# FY_-_OPTO_BOARD_3_GEN.net
KiCad netlist of a schematic drawn in EAGLE
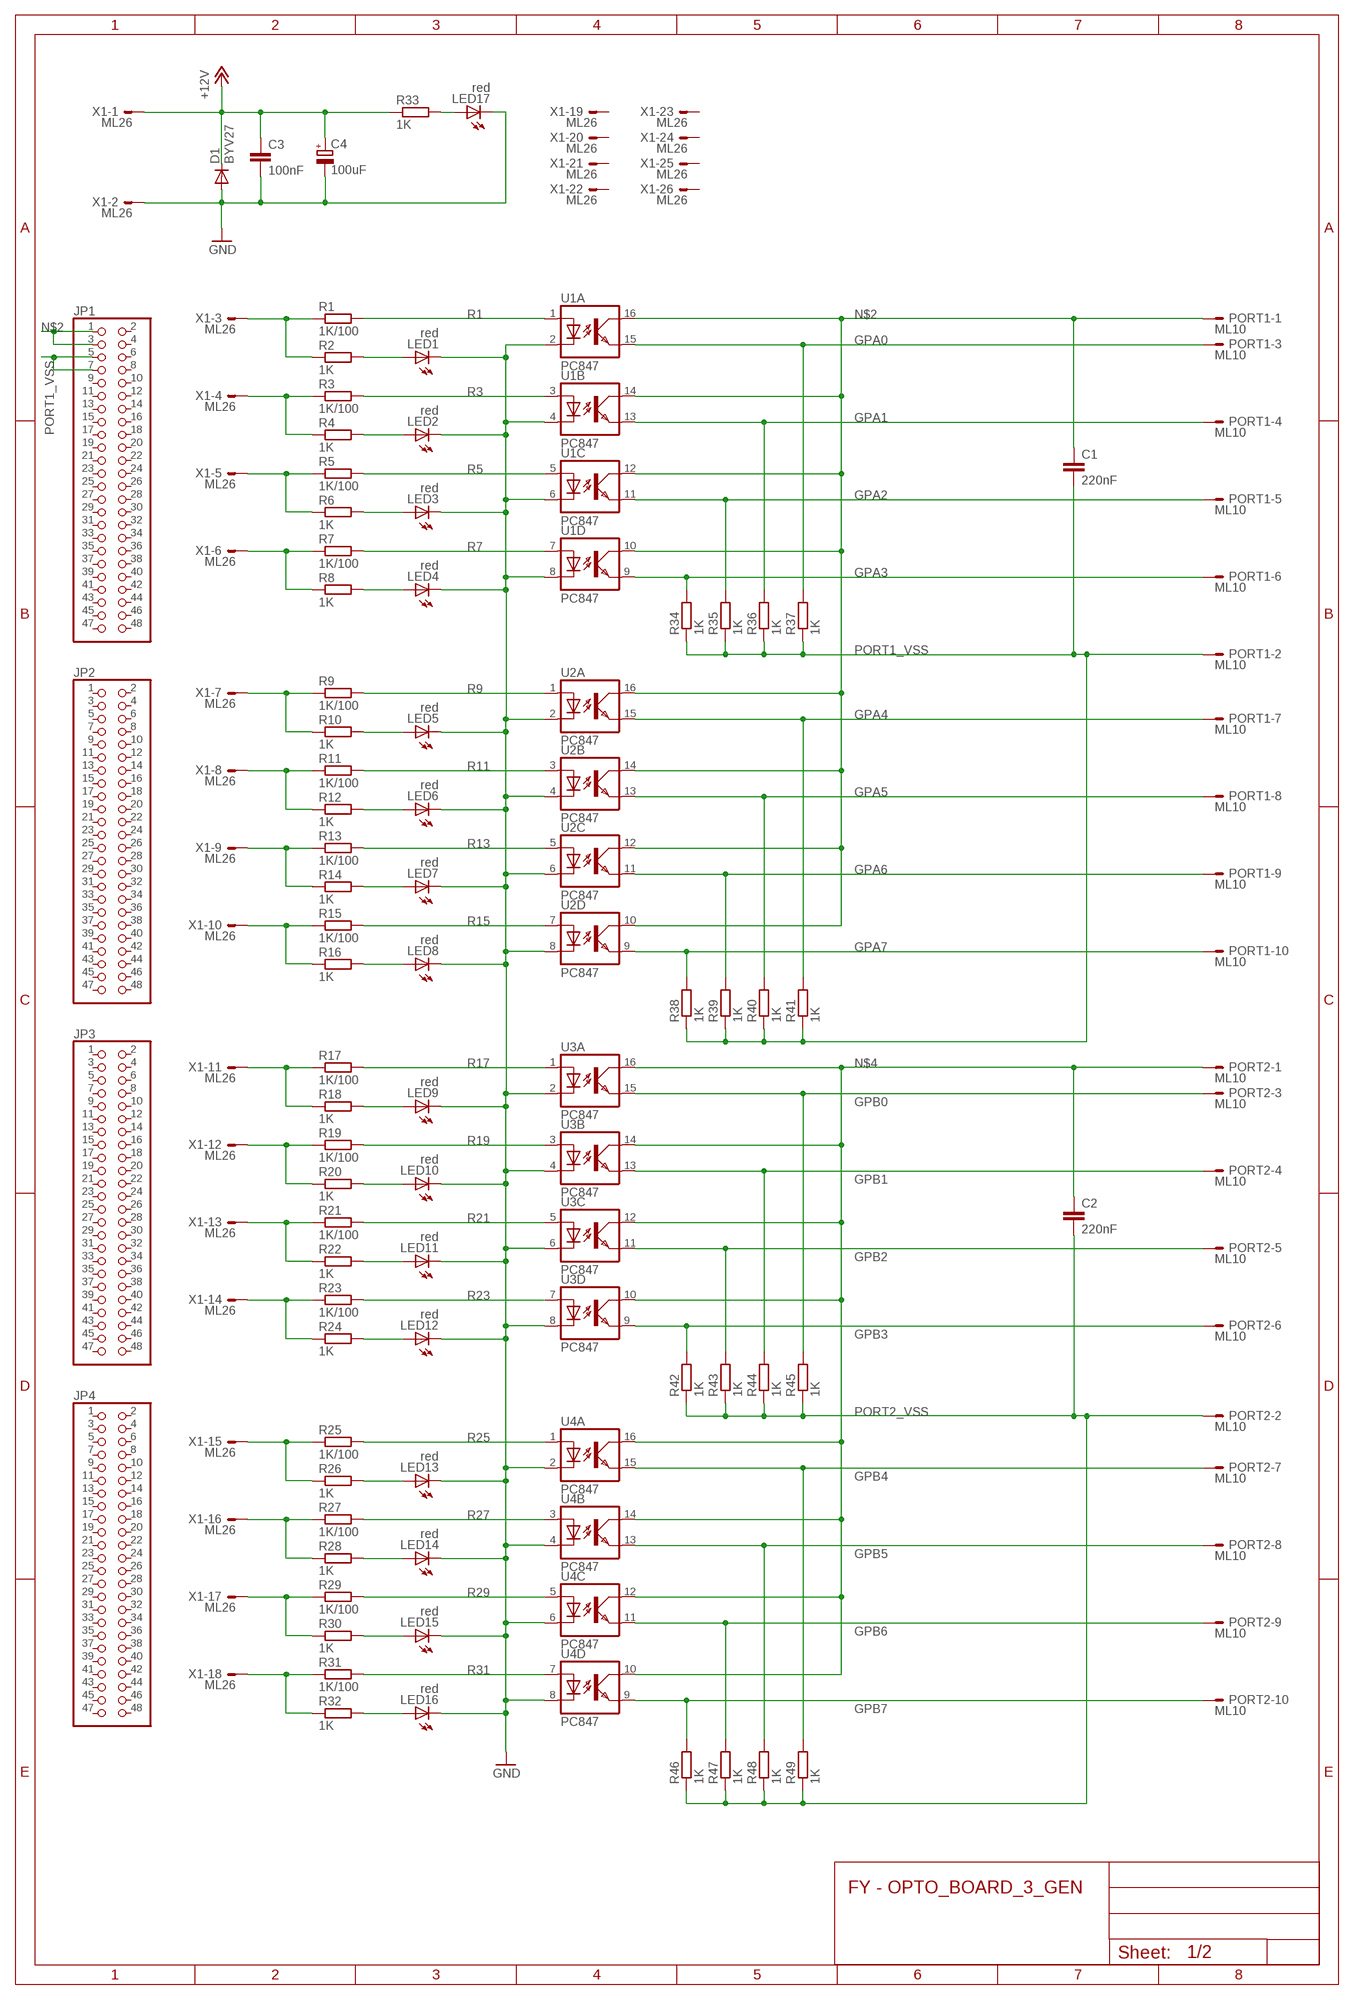
[diagram p0: schematic, sheet 1]
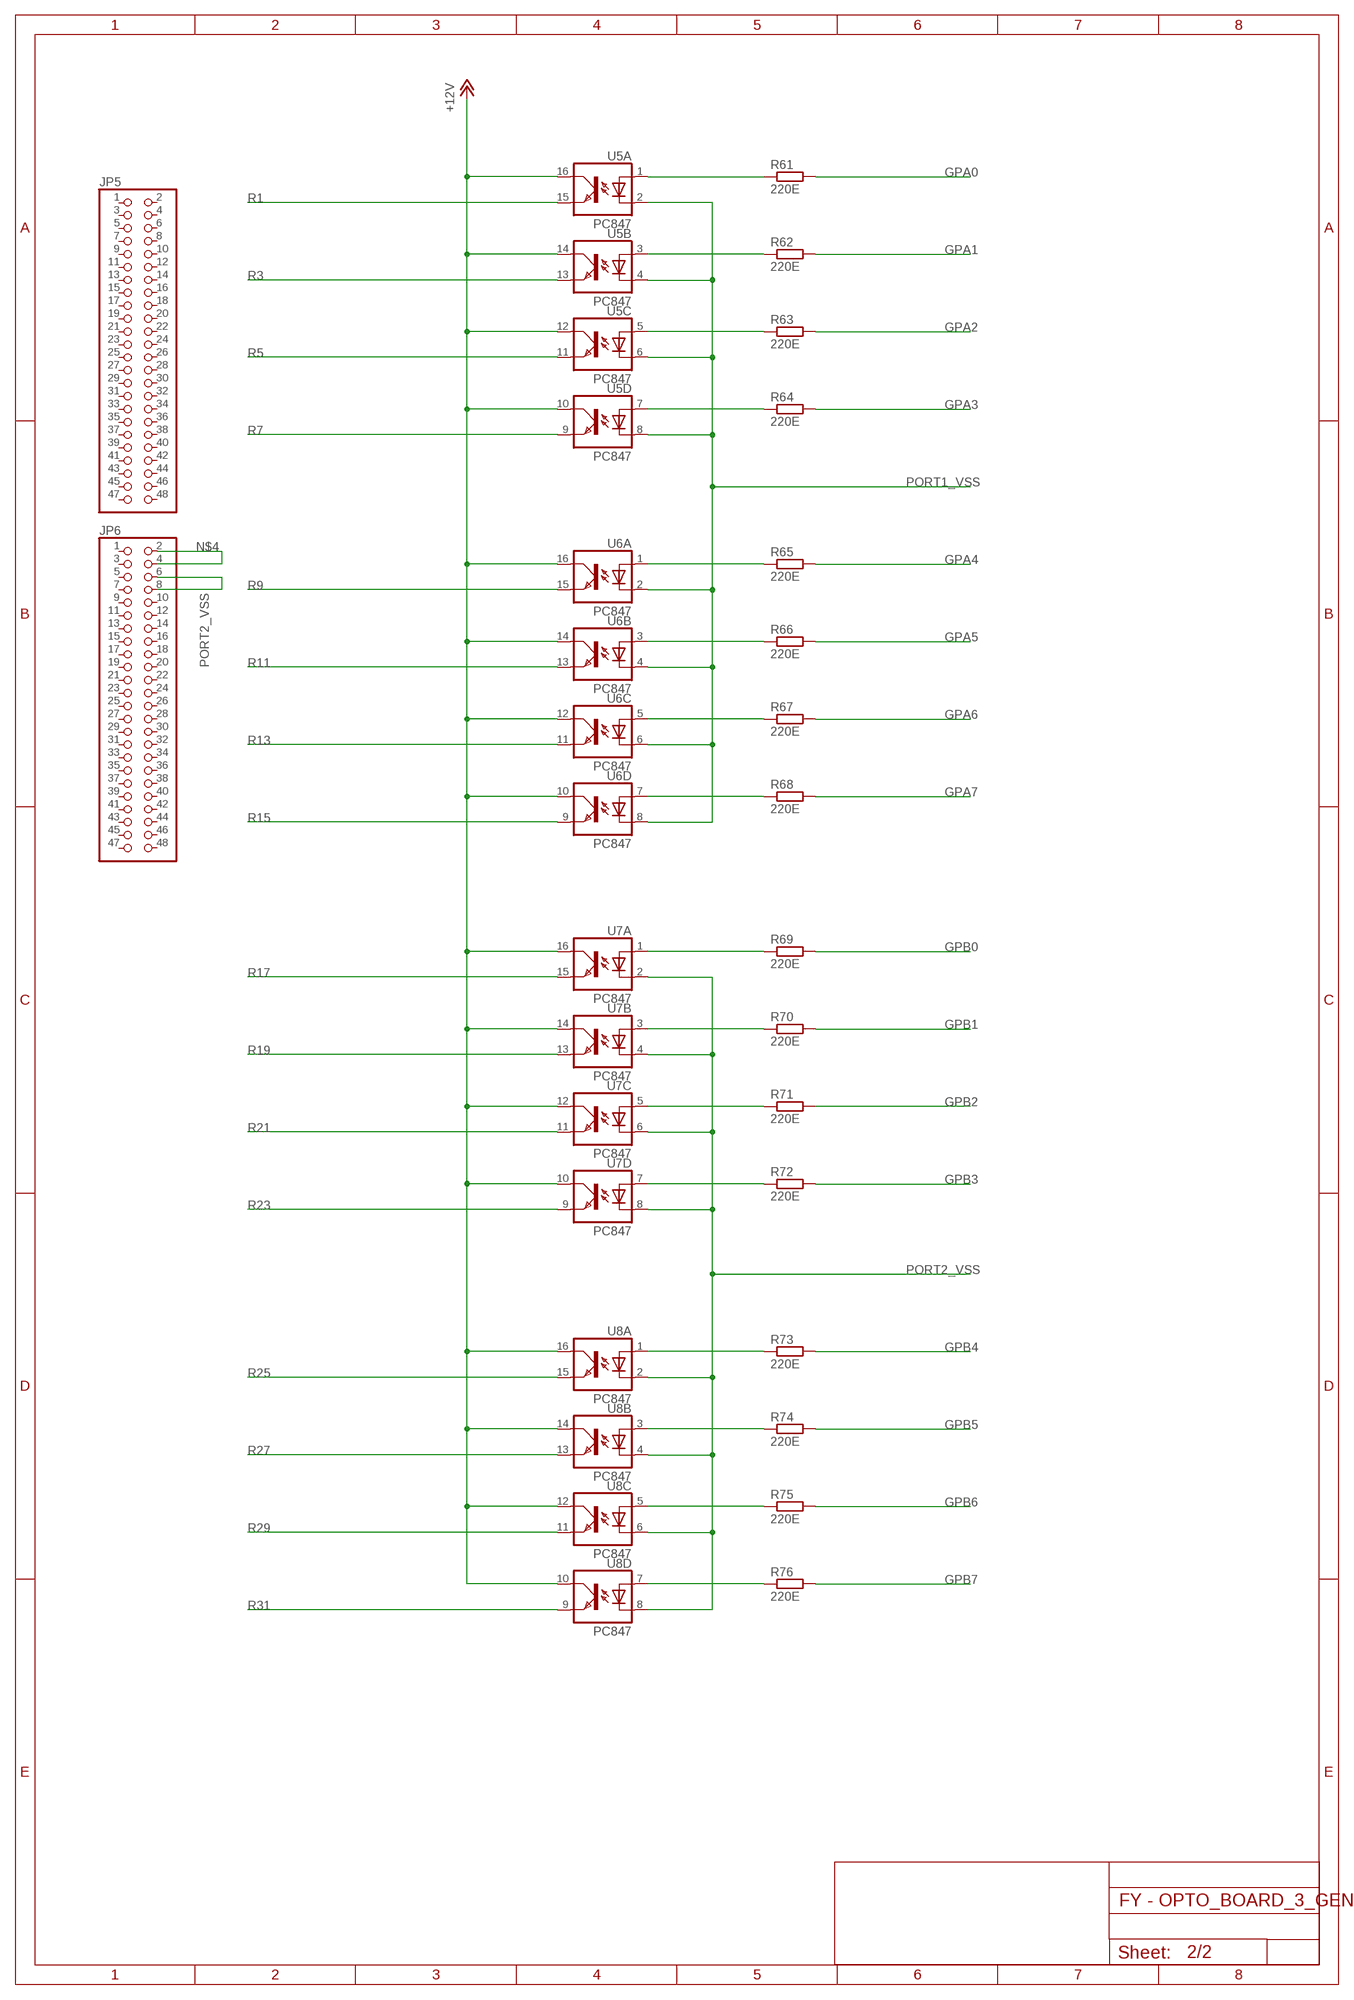
[diagram p1: schematic, sheet 2]

(export (version "E")
  (design (tool "Eeschema 10.0.6"))
  (components
    (comp (ref "JP5")
      (value "PINHD-2X24")
      (footprint "eagle-import:2X24")
      (libsource (lib "eagle-import") (part "PINHD-2X24"))
    )
    (comp (ref "JP6")
      (value "PINHD-2X24")
      (footprint "eagle-import:2X24")
      (libsource (lib "eagle-import") (part "PINHD-2X24"))
    )
    (comp (ref "R61")
      (value "220E")
      (footprint "eagle-import:0207_10")
      (libsource (lib "eagle-import") (part "R-EU_0207/10"))
    )
    (comp (ref "R62")
      (value "220E")
      (footprint "eagle-import:0207_10")
      (libsource (lib "eagle-import") (part "R-EU_0207/10"))
    )
    (comp (ref "R63")
      (value "220E")
      (footprint "eagle-import:0207_10")
      (libsource (lib "eagle-import") (part "R-EU_0207/10"))
    )
    (comp (ref "R64")
      (value "220E")
      (footprint "eagle-import:0207_10")
      (libsource (lib "eagle-import") (part "R-EU_0207/10"))
    )
    (comp (ref "R65")
      (value "220E")
      (footprint "eagle-import:0207_10")
      (libsource (lib "eagle-import") (part "R-EU_0207/10"))
    )
    (comp (ref "R66")
      (value "220E")
      (footprint "eagle-import:0207_10")
      (libsource (lib "eagle-import") (part "R-EU_0207/10"))
    )
    (comp (ref "R67")
      (value "220E")
      (footprint "eagle-import:0207_10")
      (libsource (lib "eagle-import") (part "R-EU_0207/10"))
    )
    (comp (ref "R68")
      (value "220E")
      (footprint "eagle-import:0207_10")
      (libsource (lib "eagle-import") (part "R-EU_0207/10"))
    )
    (comp (ref "R69")
      (value "220E")
      (footprint "eagle-import:0207_10")
      (libsource (lib "eagle-import") (part "R-EU_0207/10"))
    )
    (comp (ref "R70")
      (value "220E")
      (footprint "eagle-import:0207_10")
      (libsource (lib "eagle-import") (part "R-EU_0207/10"))
    )
    (comp (ref "R71")
      (value "220E")
      (footprint "eagle-import:0207_10")
      (libsource (lib "eagle-import") (part "R-EU_0207/10"))
    )
    (comp (ref "R72")
      (value "220E")
      (footprint "eagle-import:0207_10")
      (libsource (lib "eagle-import") (part "R-EU_0207/10"))
    )
    (comp (ref "R73")
      (value "220E")
      (footprint "eagle-import:0207_10")
      (libsource (lib "eagle-import") (part "R-EU_0207/10"))
    )
    (comp (ref "R74")
      (value "220E")
      (footprint "eagle-import:0207_10")
      (libsource (lib "eagle-import") (part "R-EU_0207/10"))
    )
    (comp (ref "R75")
      (value "220E")
      (footprint "eagle-import:0207_10")
      (libsource (lib "eagle-import") (part "R-EU_0207/10"))
    )
    (comp (ref "R76")
      (value "220E")
      (footprint "eagle-import:0207_10")
      (libsource (lib "eagle-import") (part "R-EU_0207/10"))
    )
    (comp (ref "U5")
      (value "PC847")
      (footprint "eagle-import:DIL16")
      (libsource (lib "eagle-import") (part "PC847"))
    )
    (comp (ref "U6")
      (value "PC847")
      (footprint "eagle-import:DIL16")
      (libsource (lib "eagle-import") (part "PC847"))
    )
    (comp (ref "U7")
      (value "PC847")
      (footprint "eagle-import:DIL16")
      (libsource (lib "eagle-import") (part "PC847"))
    )
    (comp (ref "U8")
      (value "PC847")
      (footprint "eagle-import:DIL16")
      (libsource (lib "eagle-import") (part "PC847"))
    )
    (comp (ref "C1")
      (value "220nF")
      (footprint "eagle-import:C050-025X075")
      (libsource (lib "eagle-import") (part "C-EU050-025X075"))
    )
    (comp (ref "C2")
      (value "220nF")
      (footprint "eagle-import:C050-025X075")
      (libsource (lib "eagle-import") (part "C-EU050-025X075"))
    )
    (comp (ref "C3")
      (value "100nF")
      (footprint "eagle-import:C050-025X075")
      (libsource (lib "eagle-import") (part "C-EU050-025X075"))
    )
    (comp (ref "C4")
      (value "100uF")
      (footprint "eagle-import:E5-8,5")
      (libsource (lib "eagle-import") (part "CPOL-EUE5-8.5"))
    )
    (comp (ref "D1")
      (value "BYV27")
      (footprint "eagle-import:SOD57-10")
      (libsource (lib "eagle-import") (part "BYV27"))
    )
    (comp (ref "JP1")
      (value "PINHD-2X24")
      (footprint "eagle-import:2X24")
      (libsource (lib "eagle-import") (part "PINHD-2X24"))
    )
    (comp (ref "JP2")
      (value "PINHD-2X24")
      (footprint "eagle-import:2X24")
      (libsource (lib "eagle-import") (part "PINHD-2X24"))
    )
    (comp (ref "JP3")
      (value "PINHD-2X24")
      (footprint "eagle-import:2X24")
      (libsource (lib "eagle-import") (part "PINHD-2X24"))
    )
    (comp (ref "JP4")
      (value "PINHD-2X24")
      (footprint "eagle-import:2X24")
      (libsource (lib "eagle-import") (part "PINHD-2X24"))
    )
    (comp (ref "LED1")
      (value "red")
      (footprint "eagle-import:LED3MM")
      (libsource (lib "eagle-import") (part "LED3MM"))
    )
    (comp (ref "LED2")
      (value "red")
      (footprint "eagle-import:LED3MM")
      (libsource (lib "eagle-import") (part "LED3MM"))
    )
    (comp (ref "LED3")
      (value "red")
      (footprint "eagle-import:LED3MM")
      (libsource (lib "eagle-import") (part "LED3MM"))
    )
    (comp (ref "LED4")
      (value "red")
      (footprint "eagle-import:LED3MM")
      (libsource (lib "eagle-import") (part "LED3MM"))
    )
    (comp (ref "LED5")
      (value "red")
      (footprint "eagle-import:LED3MM")
      (libsource (lib "eagle-import") (part "LED3MM"))
    )
    (comp (ref "LED6")
      (value "red")
      (footprint "eagle-import:LED3MM")
      (libsource (lib "eagle-import") (part "LED3MM"))
    )
    (comp (ref "LED7")
      (value "red")
      (footprint "eagle-import:LED3MM")
      (libsource (lib "eagle-import") (part "LED3MM"))
    )
    (comp (ref "LED8")
      (value "red")
      (footprint "eagle-import:LED3MM")
      (libsource (lib "eagle-import") (part "LED3MM"))
    )
    (comp (ref "LED9")
      (value "red")
      (footprint "eagle-import:LED3MM")
      (libsource (lib "eagle-import") (part "LED3MM"))
    )
    (comp (ref "LED10")
      (value "red")
      (footprint "eagle-import:LED3MM")
      (libsource (lib "eagle-import") (part "LED3MM"))
    )
    (comp (ref "LED11")
      (value "red")
      (footprint "eagle-import:LED3MM")
      (libsource (lib "eagle-import") (part "LED3MM"))
    )
    (comp (ref "LED12")
      (value "red")
      (footprint "eagle-import:LED3MM")
      (libsource (lib "eagle-import") (part "LED3MM"))
    )
    (comp (ref "LED13")
      (value "red")
      (footprint "eagle-import:LED3MM")
      (libsource (lib "eagle-import") (part "LED3MM"))
    )
    (comp (ref "LED14")
      (value "red")
      (footprint "eagle-import:LED3MM")
      (libsource (lib "eagle-import") (part "LED3MM"))
    )
    (comp (ref "LED15")
      (value "red")
      (footprint "eagle-import:LED3MM")
      (libsource (lib "eagle-import") (part "LED3MM"))
    )
    (comp (ref "LED16")
      (value "red")
      (footprint "eagle-import:LED3MM")
      (libsource (lib "eagle-import") (part "LED3MM"))
    )
    (comp (ref "LED17")
      (value "red")
      (footprint "eagle-import:LED3MM")
      (libsource (lib "eagle-import") (part "LED3MM"))
    )
    (comp (ref "PORT1")
      (value "ML10")
      (footprint "eagle-import:ML10")
      (libsource (lib "eagle-import") (part "ML10?E"))
    )
    (comp (ref "PORT2")
      (value "ML10")
      (footprint "eagle-import:ML10")
      (libsource (lib "eagle-import") (part "ML10?E"))
    )
    (comp (ref "R1")
      (value "1K/100")
      (footprint "eagle-import:0207_10")
      (libsource (lib "eagle-import") (part "R-EU_0207/10"))
    )
    (comp (ref "R2")
      (value "1K")
      (footprint "eagle-import:0207_10")
      (libsource (lib "eagle-import") (part "R-EU_0207/10"))
    )
    (comp (ref "R3")
      (value "1K/100")
      (footprint "eagle-import:0207_10")
      (libsource (lib "eagle-import") (part "R-EU_0207/10"))
    )
    (comp (ref "R4")
      (value "1K")
      (footprint "eagle-import:0207_10")
      (libsource (lib "eagle-import") (part "R-EU_0207/10"))
    )
    (comp (ref "R5")
      (value "1K/100")
      (footprint "eagle-import:0207_10")
      (libsource (lib "eagle-import") (part "R-EU_0207/10"))
    )
    (comp (ref "R6")
      (value "1K")
      (footprint "eagle-import:0207_10")
      (libsource (lib "eagle-import") (part "R-EU_0207/10"))
    )
    (comp (ref "R7")
      (value "1K/100")
      (footprint "eagle-import:0207_10")
      (libsource (lib "eagle-import") (part "R-EU_0207/10"))
    )
    (comp (ref "R8")
      (value "1K")
      (footprint "eagle-import:0207_10")
      (libsource (lib "eagle-import") (part "R-EU_0207/10"))
    )
    (comp (ref "R9")
      (value "1K/100")
      (footprint "eagle-import:0207_10")
      (libsource (lib "eagle-import") (part "R-EU_0207/10"))
    )
    (comp (ref "R10")
      (value "1K")
      (footprint "eagle-import:0207_10")
      (libsource (lib "eagle-import") (part "R-EU_0207/10"))
    )
    (comp (ref "R11")
      (value "1K/100")
      (footprint "eagle-import:0207_10")
      (libsource (lib "eagle-import") (part "R-EU_0207/10"))
    )
    (comp (ref "R12")
      (value "1K")
      (footprint "eagle-import:0207_10")
      (libsource (lib "eagle-import") (part "R-EU_0207/10"))
    )
    (comp (ref "R13")
      (value "1K/100")
      (footprint "eagle-import:0207_10")
      (libsource (lib "eagle-import") (part "R-EU_0207/10"))
    )
    (comp (ref "R14")
      (value "1K")
      (footprint "eagle-import:0207_10")
      (libsource (lib "eagle-import") (part "R-EU_0207/10"))
    )
    (comp (ref "R15")
      (value "1K/100")
      (footprint "eagle-import:0207_10")
      (libsource (lib "eagle-import") (part "R-EU_0207/10"))
    )
    (comp (ref "R16")
      (value "1K")
      (footprint "eagle-import:0207_10")
      (libsource (lib "eagle-import") (part "R-EU_0207/10"))
    )
    (comp (ref "R17")
      (value "1K/100")
      (footprint "eagle-import:0207_10")
      (libsource (lib "eagle-import") (part "R-EU_0207/10"))
    )
    (comp (ref "R18")
      (value "1K")
      (footprint "eagle-import:0207_10")
      (libsource (lib "eagle-import") (part "R-EU_0207/10"))
    )
    (comp (ref "R19")
      (value "1K/100")
      (footprint "eagle-import:0207_10")
      (libsource (lib "eagle-import") (part "R-EU_0207/10"))
    )
    (comp (ref "R20")
      (value "1K")
      (footprint "eagle-import:0207_10")
      (libsource (lib "eagle-import") (part "R-EU_0207/10"))
    )
    (comp (ref "R21")
      (value "1K/100")
      (footprint "eagle-import:0207_10")
      (libsource (lib "eagle-import") (part "R-EU_0207/10"))
    )
    (comp (ref "R22")
      (value "1K")
      (footprint "eagle-import:0207_10")
      (libsource (lib "eagle-import") (part "R-EU_0207/10"))
    )
    (comp (ref "R23")
      (value "1K/100")
      (footprint "eagle-import:0207_10")
      (libsource (lib "eagle-import") (part "R-EU_0207/10"))
    )
    (comp (ref "R24")
      (value "1K")
      (footprint "eagle-import:0207_10")
      (libsource (lib "eagle-import") (part "R-EU_0207/10"))
    )
    (comp (ref "R25")
      (value "1K/100")
      (footprint "eagle-import:0207_10")
      (libsource (lib "eagle-import") (part "R-EU_0207/10"))
    )
    (comp (ref "R26")
      (value "1K")
      (footprint "eagle-import:0207_10")
      (libsource (lib "eagle-import") (part "R-EU_0207/10"))
    )
    (comp (ref "R27")
      (value "1K/100")
      (footprint "eagle-import:0207_10")
      (libsource (lib "eagle-import") (part "R-EU_0207/10"))
    )
    (comp (ref "R28")
      (value "1K")
      (footprint "eagle-import:0207_10")
      (libsource (lib "eagle-import") (part "R-EU_0207/10"))
    )
    (comp (ref "R29")
      (value "1K/100")
      (footprint "eagle-import:0207_10")
      (libsource (lib "eagle-import") (part "R-EU_0207/10"))
    )
    (comp (ref "R30")
      (value "1K")
      (footprint "eagle-import:0207_10")
      (libsource (lib "eagle-import") (part "R-EU_0207/10"))
    )
    (comp (ref "R31")
      (value "1K/100")
      (footprint "eagle-import:0207_10")
      (libsource (lib "eagle-import") (part "R-EU_0207/10"))
    )
    (comp (ref "R32")
      (value "1K")
      (footprint "eagle-import:0207_10")
      (libsource (lib "eagle-import") (part "R-EU_0207/10"))
    )
    (comp (ref "R33")
      (value "1K")
      (footprint "eagle-import:0207_10")
      (libsource (lib "eagle-import") (part "R-EU_0207/10"))
    )
    (comp (ref "R34")
      (value "1K")
      (footprint "eagle-import:0207_10")
      (libsource (lib "eagle-import") (part "R-EU_0207/10"))
    )
    (comp (ref "R35")
      (value "1K")
      (footprint "eagle-import:0207_10")
      (libsource (lib "eagle-import") (part "R-EU_0207/10"))
    )
    (comp (ref "R36")
      (value "1K")
      (footprint "eagle-import:0207_10")
      (libsource (lib "eagle-import") (part "R-EU_0207/10"))
    )
    (comp (ref "R37")
      (value "1K")
      (footprint "eagle-import:0207_10")
      (libsource (lib "eagle-import") (part "R-EU_0207/10"))
    )
    (comp (ref "R38")
      (value "1K")
      (footprint "eagle-import:0207_10")
      (libsource (lib "eagle-import") (part "R-EU_0207/10"))
    )
    (comp (ref "R39")
      (value "1K")
      (footprint "eagle-import:0207_10")
      (libsource (lib "eagle-import") (part "R-EU_0207/10"))
    )
    (comp (ref "R40")
      (value "1K")
      (footprint "eagle-import:0207_10")
      (libsource (lib "eagle-import") (part "R-EU_0207/10"))
    )
    (comp (ref "R41")
      (value "1K")
      (footprint "eagle-import:0207_10")
      (libsource (lib "eagle-import") (part "R-EU_0207/10"))
    )
    (comp (ref "R42")
      (value "1K")
      (footprint "eagle-import:0207_10")
      (libsource (lib "eagle-import") (part "R-EU_0207/10"))
    )
    (comp (ref "R43")
      (value "1K")
      (footprint "eagle-import:0207_10")
      (libsource (lib "eagle-import") (part "R-EU_0207/10"))
    )
    (comp (ref "R44")
      (value "1K")
      (footprint "eagle-import:0207_10")
      (libsource (lib "eagle-import") (part "R-EU_0207/10"))
    )
    (comp (ref "R45")
      (value "1K")
      (footprint "eagle-import:0207_10")
      (libsource (lib "eagle-import") (part "R-EU_0207/10"))
    )
    (comp (ref "R46")
      (value "1K")
      (footprint "eagle-import:0207_10")
      (libsource (lib "eagle-import") (part "R-EU_0207/10"))
    )
    (comp (ref "R47")
      (value "1K")
      (footprint "eagle-import:0207_10")
      (libsource (lib "eagle-import") (part "R-EU_0207/10"))
    )
    (comp (ref "R48")
      (value "1K")
      (footprint "eagle-import:0207_10")
      (libsource (lib "eagle-import") (part "R-EU_0207/10"))
    )
    (comp (ref "R49")
      (value "1K")
      (footprint "eagle-import:0207_10")
      (libsource (lib "eagle-import") (part "R-EU_0207/10"))
    )
    (comp (ref "U1")
      (value "PC847")
      (footprint "eagle-import:DIL16")
      (libsource (lib "eagle-import") (part "PC847"))
    )
    (comp (ref "U2")
      (value "PC847")
      (footprint "eagle-import:DIL16")
      (libsource (lib "eagle-import") (part "PC847"))
    )
    (comp (ref "U3")
      (value "PC847")
      (footprint "eagle-import:DIL16")
      (libsource (lib "eagle-import") (part "PC847"))
    )
    (comp (ref "U4")
      (value "PC847")
      (footprint "eagle-import:DIL16")
      (libsource (lib "eagle-import") (part "PC847"))
    )
    (comp (ref "X1")
      (value "ML26")
      (footprint "eagle-import:ML26")
      (libsource (lib "eagle-import") (part "ML26?E"))
    )
  )
  (nets
    (net (code "1") (name "+12V") (class "Default")
      (node (ref "C3") (pin "1") (pinfunction "1_1") (pintype "passive"))
      (node (ref "C4") (pin "+") (pinfunction "+_+") (pintype "passive"))
      (node (ref "D1") (pin "C") (pinfunction "C_C") (pintype "passive"))
      (node (ref "R33") (pin "1") (pinfunction "1_1") (pintype "passive"))
      (node (ref "U5") (pin "10") (pinfunction "COL_10") (pintype "passive"))
      (node (ref "U5") (pin "12") (pinfunction "COL_12") (pintype "passive"))
      (node (ref "U5") (pin "14") (pinfunction "COL_14") (pintype "passive"))
      (node (ref "U5") (pin "16") (pinfunction "COL_16") (pintype "passive"))
      (node (ref "U6") (pin "10") (pinfunction "COL_10") (pintype "passive"))
      (node (ref "U6") (pin "12") (pinfunction "COL_12") (pintype "passive"))
      (node (ref "U6") (pin "14") (pinfunction "COL_14") (pintype "passive"))
      (node (ref "U6") (pin "16") (pinfunction "COL_16") (pintype "passive"))
      (node (ref "U7") (pin "10") (pinfunction "COL_10") (pintype "passive"))
      (node (ref "U7") (pin "12") (pinfunction "COL_12") (pintype "passive"))
      (node (ref "U7") (pin "14") (pinfunction "COL_14") (pintype "passive"))
      (node (ref "U7") (pin "16") (pinfunction "COL_16") (pintype "passive"))
      (node (ref "U8") (pin "10") (pinfunction "COL_10") (pintype "passive"))
      (node (ref "U8") (pin "12") (pinfunction "COL_12") (pintype "passive"))
      (node (ref "U8") (pin "14") (pinfunction "COL_14") (pintype "passive"))
      (node (ref "U8") (pin "16") (pinfunction "COL_16") (pintype "passive"))
      (node (ref "X1") (pin "1") (pinfunction "S_1") (pintype "passive"))
    )
    (net (code "2") (name "GND") (class "Default")
      (node (ref "C3") (pin "2") (pinfunction "2_2") (pintype "passive"))
      (node (ref "C4") (pin "-") (pinfunction "-_-") (pintype "passive"))
      (node (ref "D1") (pin "A") (pinfunction "A_A") (pintype "passive"))
      (node (ref "LED1") (pin "K") (pinfunction "C_K") (pintype "passive"))
      (node (ref "LED10") (pin "K") (pinfunction "C_K") (pintype "passive"))
      (node (ref "LED11") (pin "K") (pinfunction "C_K") (pintype "passive"))
      (node (ref "LED12") (pin "K") (pinfunction "C_K") (pintype "passive"))
      (node (ref "LED13") (pin "K") (pinfunction "C_K") (pintype "passive"))
      (node (ref "LED14") (pin "K") (pinfunction "C_K") (pintype "passive"))
      (node (ref "LED15") (pin "K") (pinfunction "C_K") (pintype "passive"))
      (node (ref "LED16") (pin "K") (pinfunction "C_K") (pintype "passive"))
      (node (ref "LED17") (pin "K") (pinfunction "C_K") (pintype "passive"))
      (node (ref "LED2") (pin "K") (pinfunction "C_K") (pintype "passive"))
      (node (ref "LED3") (pin "K") (pinfunction "C_K") (pintype "passive"))
      (node (ref "LED4") (pin "K") (pinfunction "C_K") (pintype "passive"))
      (node (ref "LED5") (pin "K") (pinfunction "C_K") (pintype "passive"))
      (node (ref "LED6") (pin "K") (pinfunction "C_K") (pintype "passive"))
      (node (ref "LED7") (pin "K") (pinfunction "C_K") (pintype "passive"))
      (node (ref "LED8") (pin "K") (pinfunction "C_K") (pintype "passive"))
      (node (ref "LED9") (pin "K") (pinfunction "C_K") (pintype "passive"))
      (node (ref "U1") (pin "2") (pinfunction "C_2") (pintype "passive"))
      (node (ref "U1") (pin "4") (pinfunction "C_4") (pintype "passive"))
      (node (ref "U1") (pin "6") (pinfunction "C_6") (pintype "passive"))
      (node (ref "U1") (pin "8") (pinfunction "C_8") (pintype "passive"))
      (node (ref "U2") (pin "2") (pinfunction "C_2") (pintype "passive"))
      (node (ref "U2") (pin "4") (pinfunction "C_4") (pintype "passive"))
      (node (ref "U2") (pin "6") (pinfunction "C_6") (pintype "passive"))
      (node (ref "U2") (pin "8") (pinfunction "C_8") (pintype "passive"))
      (node (ref "U3") (pin "2") (pinfunction "C_2") (pintype "passive"))
      (node (ref "U3") (pin "4") (pinfunction "C_4") (pintype "passive"))
      (node (ref "U3") (pin "6") (pinfunction "C_6") (pintype "passive"))
      (node (ref "U3") (pin "8") (pinfunction "C_8") (pintype "passive"))
      (node (ref "U4") (pin "2") (pinfunction "C_2") (pintype "passive"))
      (node (ref "U4") (pin "4") (pinfunction "C_4") (pintype "passive"))
      (node (ref "U4") (pin "6") (pinfunction "C_6") (pintype "passive"))
      (node (ref "U4") (pin "8") (pinfunction "C_8") (pintype "passive"))
      (node (ref "X1") (pin "2") (pinfunction "S_2") (pintype "passive"))
    )
    (net (code "3") (name "GPA0") (class "Default")
      (node (ref "PORT1") (pin "3") (pinfunction "S_3") (pintype "passive"))
      (node (ref "R37") (pin "2") (pinfunction "2_2") (pintype "passive"))
      (node (ref "R61") (pin "2") (pinfunction "2_2") (pintype "passive"))
      (node (ref "U1") (pin "15") (pinfunction "EMIT_15") (pintype "passive"))
    )
    (net (code "4") (name "GPA1") (class "Default")
      (node (ref "PORT1") (pin "4") (pinfunction "S_4") (pintype "passive"))
      (node (ref "R36") (pin "2") (pinfunction "2_2") (pintype "passive"))
      (node (ref "R62") (pin "2") (pinfunction "2_2") (pintype "passive"))
      (node (ref "U1") (pin "13") (pinfunction "EMIT_13") (pintype "passive"))
    )
    (net (code "5") (name "GPA2") (class "Default")
      (node (ref "PORT1") (pin "5") (pinfunction "S_5") (pintype "passive"))
      (node (ref "R35") (pin "2") (pinfunction "2_2") (pintype "passive"))
      (node (ref "R63") (pin "2") (pinfunction "2_2") (pintype "passive"))
      (node (ref "U1") (pin "11") (pinfunction "EMIT_11") (pintype "passive"))
    )
    (net (code "6") (name "GPA3") (class "Default")
      (node (ref "PORT1") (pin "6") (pinfunction "S_6") (pintype "passive"))
      (node (ref "R34") (pin "2") (pinfunction "2_2") (pintype "passive"))
      (node (ref "R64") (pin "2") (pinfunction "2_2") (pintype "passive"))
      (node (ref "U1") (pin "9") (pinfunction "EMIT_9") (pintype "passive"))
    )
    (net (code "7") (name "GPA4") (class "Default")
      (node (ref "PORT1") (pin "7") (pinfunction "S_7") (pintype "passive"))
      (node (ref "R41") (pin "2") (pinfunction "2_2") (pintype "passive"))
      (node (ref "R65") (pin "2") (pinfunction "2_2") (pintype "passive"))
      (node (ref "U2") (pin "15") (pinfunction "EMIT_15") (pintype "passive"))
    )
    (net (code "8") (name "GPA5") (class "Default")
      (node (ref "PORT1") (pin "8") (pinfunction "S_8") (pintype "passive"))
      (node (ref "R40") (pin "2") (pinfunction "2_2") (pintype "passive"))
      (node (ref "R66") (pin "2") (pinfunction "2_2") (pintype "passive"))
      (node (ref "U2") (pin "13") (pinfunction "EMIT_13") (pintype "passive"))
    )
    (net (code "9") (name "GPA6") (class "Default")
      (node (ref "PORT1") (pin "9") (pinfunction "S_9") (pintype "passive"))
      (node (ref "R39") (pin "2") (pinfunction "2_2") (pintype "passive"))
      (node (ref "R67") (pin "2") (pinfunction "2_2") (pintype "passive"))
      (node (ref "U2") (pin "11") (pinfunction "EMIT_11") (pintype "passive"))
    )
    (net (code "10") (name "GPA7") (class "Default")
      (node (ref "PORT1") (pin "10") (pinfunction "S_10") (pintype "passive"))
      (node (ref "R38") (pin "2") (pinfunction "2_2") (pintype "passive"))
      (node (ref "R68") (pin "2") (pinfunction "2_2") (pintype "passive"))
      (node (ref "U2") (pin "9") (pinfunction "EMIT_9") (pintype "passive"))
    )
    (net (code "11") (name "GPB0") (class "Default")
      (node (ref "PORT2") (pin "3") (pinfunction "S_3") (pintype "passive"))
      (node (ref "R45") (pin "2") (pinfunction "2_2") (pintype "passive"))
      (node (ref "R69") (pin "2") (pinfunction "2_2") (pintype "passive"))
      (node (ref "U3") (pin "15") (pinfunction "EMIT_15") (pintype "passive"))
    )
    (net (code "12") (name "GPB1") (class "Default")
      (node (ref "PORT2") (pin "4") (pinfunction "S_4") (pintype "passive"))
      (node (ref "R44") (pin "2") (pinfunction "2_2") (pintype "passive"))
      (node (ref "R70") (pin "2") (pinfunction "2_2") (pintype "passive"))
      (node (ref "U3") (pin "13") (pinfunction "EMIT_13") (pintype "passive"))
    )
    (net (code "13") (name "GPB2") (class "Default")
      (node (ref "PORT2") (pin "5") (pinfunction "S_5") (pintype "passive"))
      (node (ref "R43") (pin "2") (pinfunction "2_2") (pintype "passive"))
      (node (ref "R71") (pin "2") (pinfunction "2_2") (pintype "passive"))
      (node (ref "U3") (pin "11") (pinfunction "EMIT_11") (pintype "passive"))
    )
    (net (code "14") (name "GPB3") (class "Default")
      (node (ref "PORT2") (pin "6") (pinfunction "S_6") (pintype "passive"))
      (node (ref "R42") (pin "2") (pinfunction "2_2") (pintype "passive"))
      (node (ref "R72") (pin "2") (pinfunction "2_2") (pintype "passive"))
      (node (ref "U3") (pin "9") (pinfunction "EMIT_9") (pintype "passive"))
    )
    (net (code "15") (name "GPB4") (class "Default")
      (node (ref "PORT2") (pin "7") (pinfunction "S_7") (pintype "passive"))
      (node (ref "R49") (pin "2") (pinfunction "2_2") (pintype "passive"))
      (node (ref "R73") (pin "2") (pinfunction "2_2") (pintype "passive"))
      (node (ref "U4") (pin "15") (pinfunction "EMIT_15") (pintype "passive"))
    )
    (net (code "16") (name "GPB5") (class "Default")
      (node (ref "PORT2") (pin "8") (pinfunction "S_8") (pintype "passive"))
      (node (ref "R48") (pin "2") (pinfunction "2_2") (pintype "passive"))
      (node (ref "R74") (pin "2") (pinfunction "2_2") (pintype "passive"))
      (node (ref "U4") (pin "13") (pinfunction "EMIT_13") (pintype "passive"))
    )
    (net (code "17") (name "GPB6") (class "Default")
      (node (ref "PORT2") (pin "9") (pinfunction "S_9") (pintype "passive"))
      (node (ref "R47") (pin "2") (pinfunction "2_2") (pintype "passive"))
      (node (ref "R75") (pin "2") (pinfunction "2_2") (pintype "passive"))
      (node (ref "U4") (pin "11") (pinfunction "EMIT_11") (pintype "passive"))
    )
    (net (code "18") (name "GPB7") (class "Default")
      (node (ref "PORT2") (pin "10") (pinfunction "S_10") (pintype "passive"))
      (node (ref "R46") (pin "2") (pinfunction "2_2") (pintype "passive"))
      (node (ref "R76") (pin "2") (pinfunction "2_2") (pintype "passive"))
      (node (ref "U4") (pin "9") (pinfunction "EMIT_9") (pintype "passive"))
    )
    (net (code "19") (name "N$2") (class "Default")
      (node (ref "C1") (pin "1") (pinfunction "1_1") (pintype "passive"))
      (node (ref "JP1") (pin "1") (pinfunction "1_1") (pintype "passive"))
      (node (ref "JP1") (pin "3") (pinfunction "3_3") (pintype "passive"))
      (node (ref "PORT1") (pin "1") (pinfunction "S_1") (pintype "passive"))
      (node (ref "U1") (pin "10") (pinfunction "COL_10") (pintype "passive"))
      (node (ref "U1") (pin "12") (pinfunction "COL_12") (pintype "passive"))
      (node (ref "U1") (pin "14") (pinfunction "COL_14") (pintype "passive"))
      (node (ref "U1") (pin "16") (pinfunction "COL_16") (pintype "passive"))
      (node (ref "U2") (pin "10") (pinfunction "COL_10") (pintype "passive"))
      (node (ref "U2") (pin "12") (pinfunction "COL_12") (pintype "passive"))
      (node (ref "U2") (pin "14") (pinfunction "COL_14") (pintype "passive"))
      (node (ref "U2") (pin "16") (pinfunction "COL_16") (pintype "passive"))
    )
    (net (code "20") (name "N$4") (class "Default")
      (node (ref "C2") (pin "1") (pinfunction "1_1") (pintype "passive"))
      (node (ref "JP6") (pin "2") (pinfunction "2_2") (pintype "passive"))
      (node (ref "JP6") (pin "4") (pinfunction "4_4") (pintype "passive"))
      (node (ref "PORT2") (pin "1") (pinfunction "S_1") (pintype "passive"))
      (node (ref "U3") (pin "10") (pinfunction "COL_10") (pintype "passive"))
      (node (ref "U3") (pin "12") (pinfunction "COL_12") (pintype "passive"))
      (node (ref "U3") (pin "14") (pinfunction "COL_14") (pintype "passive"))
      (node (ref "U3") (pin "16") (pinfunction "COL_16") (pintype "passive"))
      (node (ref "U4") (pin "10") (pinfunction "COL_10") (pintype "passive"))
      (node (ref "U4") (pin "12") (pinfunction "COL_12") (pintype "passive"))
      (node (ref "U4") (pin "14") (pinfunction "COL_14") (pintype "passive"))
      (node (ref "U4") (pin "16") (pinfunction "COL_16") (pintype "passive"))
    )
    (net (code "21") (name "Net-(LED1-PadA)") (class "Default")
      (node (ref "LED1") (pin "A") (pinfunction "A_A") (pintype "passive"))
      (node (ref "R2") (pin "2") (pinfunction "2_2") (pintype "passive"))
    )
    (net (code "22") (name "Net-(LED2-PadA)") (class "Default")
      (node (ref "LED2") (pin "A") (pinfunction "A_A") (pintype "passive"))
      (node (ref "R4") (pin "2") (pinfunction "2_2") (pintype "passive"))
    )
    (net (code "23") (name "Net-(LED3-PadA)") (class "Default")
      (node (ref "LED3") (pin "A") (pinfunction "A_A") (pintype "passive"))
      (node (ref "R6") (pin "2") (pinfunction "2_2") (pintype "passive"))
    )
    (net (code "24") (name "Net-(LED4-PadA)") (class "Default")
      (node (ref "LED4") (pin "A") (pinfunction "A_A") (pintype "passive"))
      (node (ref "R8") (pin "2") (pinfunction "2_2") (pintype "passive"))
    )
    (net (code "25") (name "Net-(LED5-PadA)") (class "Default")
      (node (ref "LED5") (pin "A") (pinfunction "A_A") (pintype "passive"))
      (node (ref "R10") (pin "2") (pinfunction "2_2") (pintype "passive"))
    )
    (net (code "26") (name "Net-(LED6-PadA)") (class "Default")
      (node (ref "LED6") (pin "A") (pinfunction "A_A") (pintype "passive"))
      (node (ref "R12") (pin "2") (pinfunction "2_2") (pintype "passive"))
    )
    (net (code "27") (name "Net-(LED7-PadA)") (class "Default")
      (node (ref "LED7") (pin "A") (pinfunction "A_A") (pintype "passive"))
      (node (ref "R14") (pin "2") (pinfunction "2_2") (pintype "passive"))
    )
    (net (code "28") (name "Net-(LED8-PadA)") (class "Default")
      (node (ref "LED8") (pin "A") (pinfunction "A_A") (pintype "passive"))
      (node (ref "R16") (pin "2") (pinfunction "2_2") (pintype "passive"))
    )
    (net (code "29") (name "Net-(LED9-PadA)") (class "Default")
      (node (ref "LED9") (pin "A") (pinfunction "A_A") (pintype "passive"))
      (node (ref "R18") (pin "2") (pinfunction "2_2") (pintype "passive"))
    )
    (net (code "30") (name "Net-(LED10-PadA)") (class "Default")
      (node (ref "LED10") (pin "A") (pinfunction "A_A") (pintype "passive"))
      (node (ref "R20") (pin "2") (pinfunction "2_2") (pintype "passive"))
    )
    (net (code "31") (name "Net-(LED11-PadA)") (class "Default")
      (node (ref "LED11") (pin "A") (pinfunction "A_A") (pintype "passive"))
      (node (ref "R22") (pin "2") (pinfunction "2_2") (pintype "passive"))
    )
    (net (code "32") (name "Net-(LED12-PadA)") (class "Default")
      (node (ref "LED12") (pin "A") (pinfunction "A_A") (pintype "passive"))
      (node (ref "R24") (pin "2") (pinfunction "2_2") (pintype "passive"))
    )
    (net (code "33") (name "Net-(LED13-PadA)") (class "Default")
      (node (ref "LED13") (pin "A") (pinfunction "A_A") (pintype "passive"))
      (node (ref "R26") (pin "2") (pinfunction "2_2") (pintype "passive"))
    )
    (net (code "34") (name "Net-(LED14-PadA)") (class "Default")
      (node (ref "LED14") (pin "A") (pinfunction "A_A") (pintype "passive"))
      (node (ref "R28") (pin "2") (pinfunction "2_2") (pintype "passive"))
    )
    (net (code "35") (name "Net-(LED15-PadA)") (class "Default")
      (node (ref "LED15") (pin "A") (pinfunction "A_A") (pintype "passive"))
      (node (ref "R30") (pin "2") (pinfunction "2_2") (pintype "passive"))
    )
    (net (code "36") (name "Net-(LED16-PadA)") (class "Default")
      (node (ref "LED16") (pin "A") (pinfunction "A_A") (pintype "passive"))
      (node (ref "R32") (pin "2") (pinfunction "2_2") (pintype "passive"))
    )
    (net (code "37") (name "Net-(LED17-PadA)") (class "Default")
      (node (ref "LED17") (pin "A") (pinfunction "A_A") (pintype "passive"))
      (node (ref "R33") (pin "2") (pinfunction "2_2") (pintype "passive"))
    )
    (net (code "38") (name "Net-(U5A-A)") (class "Default")
      (node (ref "R61") (pin "1") (pinfunction "1_1") (pintype "passive"))
      (node (ref "U5") (pin "1") (pinfunction "A_1") (pintype "passive"))
    )
    (net (code "39") (name "Net-(U5B-A)") (class "Default")
      (node (ref "R62") (pin "1") (pinfunction "1_1") (pintype "passive"))
      (node (ref "U5") (pin "3") (pinfunction "A_3") (pintype "passive"))
    )
    (net (code "40") (name "Net-(U5C-A)") (class "Default")
      (node (ref "R63") (pin "1") (pinfunction "1_1") (pintype "passive"))
      (node (ref "U5") (pin "5") (pinfunction "A_5") (pintype "passive"))
    )
    (net (code "41") (name "Net-(U5D-A)") (class "Default")
      (node (ref "R64") (pin "1") (pinfunction "1_1") (pintype "passive"))
      (node (ref "U5") (pin "7") (pinfunction "A_7") (pintype "passive"))
    )
    (net (code "42") (name "Net-(U6A-A)") (class "Default")
      (node (ref "R65") (pin "1") (pinfunction "1_1") (pintype "passive"))
      (node (ref "U6") (pin "1") (pinfunction "A_1") (pintype "passive"))
    )
    (net (code "43") (name "Net-(U6B-A)") (class "Default")
      (node (ref "R66") (pin "1") (pinfunction "1_1") (pintype "passive"))
      (node (ref "U6") (pin "3") (pinfunction "A_3") (pintype "passive"))
    )
    (net (code "44") (name "Net-(U6C-A)") (class "Default")
      (node (ref "R67") (pin "1") (pinfunction "1_1") (pintype "passive"))
      (node (ref "U6") (pin "5") (pinfunction "A_5") (pintype "passive"))
    )
    (net (code "45") (name "Net-(U6D-A)") (class "Default")
      (node (ref "R68") (pin "1") (pinfunction "1_1") (pintype "passive"))
      (node (ref "U6") (pin "7") (pinfunction "A_7") (pintype "passive"))
    )
    (net (code "46") (name "Net-(U7A-A)") (class "Default")
      (node (ref "R69") (pin "1") (pinfunction "1_1") (pintype "passive"))
      (node (ref "U7") (pin "1") (pinfunction "A_1") (pintype "passive"))
    )
    (net (code "47") (name "Net-(U7B-A)") (class "Default")
      (node (ref "R70") (pin "1") (pinfunction "1_1") (pintype "passive"))
      (node (ref "U7") (pin "3") (pinfunction "A_3") (pintype "passive"))
    )
    (net (code "48") (name "Net-(U7C-A)") (class "Default")
      (node (ref "R71") (pin "1") (pinfunction "1_1") (pintype "passive"))
      (node (ref "U7") (pin "5") (pinfunction "A_5") (pintype "passive"))
    )
    (net (code "49") (name "Net-(U7D-A)") (class "Default")
      (node (ref "R72") (pin "1") (pinfunction "1_1") (pintype "passive"))
      (node (ref "U7") (pin "7") (pinfunction "A_7") (pintype "passive"))
    )
    (net (code "50") (name "Net-(U8A-A)") (class "Default")
      (node (ref "R73") (pin "1") (pinfunction "1_1") (pintype "passive"))
      (node (ref "U8") (pin "1") (pinfunction "A_1") (pintype "passive"))
    )
    (net (code "51") (name "Net-(U8B-A)") (class "Default")
      (node (ref "R74") (pin "1") (pinfunction "1_1") (pintype "passive"))
      (node (ref "U8") (pin "3") (pinfunction "A_3") (pintype "passive"))
    )
    (net (code "52") (name "Net-(U8C-A)") (class "Default")
      (node (ref "R75") (pin "1") (pinfunction "1_1") (pintype "passive"))
      (node (ref "U8") (pin "5") (pinfunction "A_5") (pintype "passive"))
    )
    (net (code "53") (name "Net-(U8D-A)") (class "Default")
      (node (ref "R76") (pin "1") (pinfunction "1_1") (pintype "passive"))
      (node (ref "U8") (pin "7") (pinfunction "A_7") (pintype "passive"))
    )
    (net (code "54") (name "Net-(X1B-S)") (class "Default")
      (node (ref "R15") (pin "1") (pinfunction "1_1") (pintype "passive"))
      (node (ref "R16") (pin "1") (pinfunction "1_1") (pintype "passive"))
      (node (ref "X1") (pin "10") (pinfunction "S_10") (pintype "passive"))
    )
    (net (code "55") (name "Net-(X1C-S)") (class "Default")
      (node (ref "R17") (pin "1") (pinfunction "1_1") (pintype "passive"))
      (node (ref "R18") (pin "1") (pinfunction "1_1") (pintype "passive"))
      (node (ref "X1") (pin "11") (pinfunction "S_11") (pintype "passive"))
    )
    (net (code "56") (name "Net-(X1D-S)") (class "Default")
      (node (ref "R19") (pin "1") (pinfunction "1_1") (pintype "passive"))
      (node (ref "R20") (pin "1") (pinfunction "1_1") (pintype "passive"))
      (node (ref "X1") (pin "12") (pinfunction "S_12") (pintype "passive"))
    )
    (net (code "57") (name "Net-(X1E-S)") (class "Default")
      (node (ref "R21") (pin "1") (pinfunction "1_1") (pintype "passive"))
      (node (ref "R22") (pin "1") (pinfunction "1_1") (pintype "passive"))
      (node (ref "X1") (pin "13") (pinfunction "S_13") (pintype "passive"))
    )
    (net (code "58") (name "Net-(X1F-S)") (class "Default")
      (node (ref "R23") (pin "1") (pinfunction "1_1") (pintype "passive"))
      (node (ref "R24") (pin "1") (pinfunction "1_1") (pintype "passive"))
      (node (ref "X1") (pin "14") (pinfunction "S_14") (pintype "passive"))
    )
    (net (code "59") (name "Net-(X1G-S)") (class "Default")
      (node (ref "R25") (pin "1") (pinfunction "1_1") (pintype "passive"))
      (node (ref "R26") (pin "1") (pinfunction "1_1") (pintype "passive"))
      (node (ref "X1") (pin "15") (pinfunction "S_15") (pintype "passive"))
    )
    (net (code "60") (name "Net-(X1H-S)") (class "Default")
      (node (ref "R27") (pin "1") (pinfunction "1_1") (pintype "passive"))
      (node (ref "R28") (pin "1") (pinfunction "1_1") (pintype "passive"))
      (node (ref "X1") (pin "16") (pinfunction "S_16") (pintype "passive"))
    )
    (net (code "61") (name "Net-(X1I-S)") (class "Default")
      (node (ref "R29") (pin "1") (pinfunction "1_1") (pintype "passive"))
      (node (ref "R30") (pin "1") (pinfunction "1_1") (pintype "passive"))
      (node (ref "X1") (pin "17") (pinfunction "S_17") (pintype "passive"))
    )
    (net (code "62") (name "Net-(X1J-S)") (class "Default")
      (node (ref "R31") (pin "1") (pinfunction "1_1") (pintype "passive"))
      (node (ref "R32") (pin "1") (pinfunction "1_1") (pintype "passive"))
      (node (ref "X1") (pin "18") (pinfunction "S_18") (pintype "passive"))
    )
    (net (code "63") (name "Net-(X1T-S)") (class "Default")
      (node (ref "R1") (pin "1") (pinfunction "1_1") (pintype "passive"))
      (node (ref "R2") (pin "1") (pinfunction "1_1") (pintype "passive"))
      (node (ref "X1") (pin "3") (pinfunction "S_3") (pintype "passive"))
    )
    (net (code "64") (name "Net-(X1U-S)") (class "Default")
      (node (ref "R3") (pin "1") (pinfunction "1_1") (pintype "passive"))
      (node (ref "R4") (pin "1") (pinfunction "1_1") (pintype "passive"))
      (node (ref "X1") (pin "4") (pinfunction "S_4") (pintype "passive"))
    )
    (net (code "65") (name "Net-(X1V-S)") (class "Default")
      (node (ref "R5") (pin "1") (pinfunction "1_1") (pintype "passive"))
      (node (ref "R6") (pin "1") (pinfunction "1_1") (pintype "passive"))
      (node (ref "X1") (pin "5") (pinfunction "S_5") (pintype "passive"))
    )
    (net (code "66") (name "Net-(X1W-S)") (class "Default")
      (node (ref "R7") (pin "1") (pinfunction "1_1") (pintype "passive"))
      (node (ref "R8") (pin "1") (pinfunction "1_1") (pintype "passive"))
      (node (ref "X1") (pin "6") (pinfunction "S_6") (pintype "passive"))
    )
    (net (code "67") (name "Net-(X1X-S)") (class "Default")
      (node (ref "R10") (pin "1") (pinfunction "1_1") (pintype "passive"))
      (node (ref "R9") (pin "1") (pinfunction "1_1") (pintype "passive"))
      (node (ref "X1") (pin "7") (pinfunction "S_7") (pintype "passive"))
    )
    (net (code "68") (name "Net-(X1Y-S)") (class "Default")
      (node (ref "R11") (pin "1") (pinfunction "1_1") (pintype "passive"))
      (node (ref "R12") (pin "1") (pinfunction "1_1") (pintype "passive"))
      (node (ref "X1") (pin "8") (pinfunction "S_8") (pintype "passive"))
    )
    (net (code "69") (name "Net-(X1Z-S)") (class "Default")
      (node (ref "R13") (pin "1") (pinfunction "1_1") (pintype "passive"))
      (node (ref "R14") (pin "1") (pinfunction "1_1") (pintype "passive"))
      (node (ref "X1") (pin "9") (pinfunction "S_9") (pintype "passive"))
    )
    (net (code "70") (name "PORT1_VSS") (class "Default")
      (node (ref "C1") (pin "2") (pinfunction "2_2") (pintype "passive"))
      (node (ref "JP1") (pin "5") (pinfunction "5_5") (pintype "passive"))
      (node (ref "JP1") (pin "7") (pinfunction "7_7") (pintype "passive"))
      (node (ref "PORT1") (pin "2") (pinfunction "S_2") (pintype "passive"))
      (node (ref "R34") (pin "1") (pinfunction "1_1") (pintype "passive"))
      (node (ref "R35") (pin "1") (pinfunction "1_1") (pintype "passive"))
      (node (ref "R36") (pin "1") (pinfunction "1_1") (pintype "passive"))
      (node (ref "R37") (pin "1") (pinfunction "1_1") (pintype "passive"))
      (node (ref "R38") (pin "1") (pinfunction "1_1") (pintype "passive"))
      (node (ref "R39") (pin "1") (pinfunction "1_1") (pintype "passive"))
      (node (ref "R40") (pin "1") (pinfunction "1_1") (pintype "passive"))
      (node (ref "R41") (pin "1") (pinfunction "1_1") (pintype "passive"))
      (node (ref "U5") (pin "2") (pinfunction "C_2") (pintype "passive"))
      (node (ref "U5") (pin "4") (pinfunction "C_4") (pintype "passive"))
      (node (ref "U5") (pin "6") (pinfunction "C_6") (pintype "passive"))
      (node (ref "U5") (pin "8") (pinfunction "C_8") (pintype "passive"))
      (node (ref "U6") (pin "2") (pinfunction "C_2") (pintype "passive"))
      (node (ref "U6") (pin "4") (pinfunction "C_4") (pintype "passive"))
      (node (ref "U6") (pin "6") (pinfunction "C_6") (pintype "passive"))
      (node (ref "U6") (pin "8") (pinfunction "C_8") (pintype "passive"))
    )
    (net (code "71") (name "PORT2_VSS") (class "Default")
      (node (ref "C2") (pin "2") (pinfunction "2_2") (pintype "passive"))
      (node (ref "JP6") (pin "6") (pinfunction "6_6") (pintype "passive"))
      (node (ref "JP6") (pin "8") (pinfunction "8_8") (pintype "passive"))
      (node (ref "PORT2") (pin "2") (pinfunction "S_2") (pintype "passive"))
      (node (ref "R42") (pin "1") (pinfunction "1_1") (pintype "passive"))
      (node (ref "R43") (pin "1") (pinfunction "1_1") (pintype "passive"))
      (node (ref "R44") (pin "1") (pinfunction "1_1") (pintype "passive"))
      (node (ref "R45") (pin "1") (pinfunction "1_1") (pintype "passive"))
      (node (ref "R46") (pin "1") (pinfunction "1_1") (pintype "passive"))
      (node (ref "R47") (pin "1") (pinfunction "1_1") (pintype "passive"))
      (node (ref "R48") (pin "1") (pinfunction "1_1") (pintype "passive"))
      (node (ref "R49") (pin "1") (pinfunction "1_1") (pintype "passive"))
      (node (ref "U7") (pin "2") (pinfunction "C_2") (pintype "passive"))
      (node (ref "U7") (pin "4") (pinfunction "C_4") (pintype "passive"))
      (node (ref "U7") (pin "6") (pinfunction "C_6") (pintype "passive"))
      (node (ref "U7") (pin "8") (pinfunction "C_8") (pintype "passive"))
      (node (ref "U8") (pin "2") (pinfunction "C_2") (pintype "passive"))
      (node (ref "U8") (pin "4") (pinfunction "C_4") (pintype "passive"))
      (node (ref "U8") (pin "6") (pinfunction "C_6") (pintype "passive"))
      (node (ref "U8") (pin "8") (pinfunction "C_8") (pintype "passive"))
    )
    (net (code "72") (name "R1") (class "Default")
      (node (ref "R1") (pin "2") (pinfunction "2_2") (pintype "passive"))
      (node (ref "U1") (pin "1") (pinfunction "A_1") (pintype "passive"))
      (node (ref "U5") (pin "15") (pinfunction "EMIT_15") (pintype "passive"))
    )
    (net (code "73") (name "R3") (class "Default")
      (node (ref "R3") (pin "2") (pinfunction "2_2") (pintype "passive"))
      (node (ref "U1") (pin "3") (pinfunction "A_3") (pintype "passive"))
      (node (ref "U5") (pin "13") (pinfunction "EMIT_13") (pintype "passive"))
    )
    (net (code "74") (name "R5") (class "Default")
      (node (ref "R5") (pin "2") (pinfunction "2_2") (pintype "passive"))
      (node (ref "U1") (pin "5") (pinfunction "A_5") (pintype "passive"))
      (node (ref "U5") (pin "11") (pinfunction "EMIT_11") (pintype "passive"))
    )
    (net (code "75") (name "R7") (class "Default")
      (node (ref "R7") (pin "2") (pinfunction "2_2") (pintype "passive"))
      (node (ref "U1") (pin "7") (pinfunction "A_7") (pintype "passive"))
      (node (ref "U5") (pin "9") (pinfunction "EMIT_9") (pintype "passive"))
    )
    (net (code "76") (name "R9") (class "Default")
      (node (ref "R9") (pin "2") (pinfunction "2_2") (pintype "passive"))
      (node (ref "U2") (pin "1") (pinfunction "A_1") (pintype "passive"))
      (node (ref "U6") (pin "15") (pinfunction "EMIT_15") (pintype "passive"))
    )
    (net (code "77") (name "R11") (class "Default")
      (node (ref "R11") (pin "2") (pinfunction "2_2") (pintype "passive"))
      (node (ref "U2") (pin "3") (pinfunction "A_3") (pintype "passive"))
      (node (ref "U6") (pin "13") (pinfunction "EMIT_13") (pintype "passive"))
    )
    (net (code "78") (name "R13") (class "Default")
      (node (ref "R13") (pin "2") (pinfunction "2_2") (pintype "passive"))
      (node (ref "U2") (pin "5") (pinfunction "A_5") (pintype "passive"))
      (node (ref "U6") (pin "11") (pinfunction "EMIT_11") (pintype "passive"))
    )
    (net (code "79") (name "R15") (class "Default")
      (node (ref "R15") (pin "2") (pinfunction "2_2") (pintype "passive"))
      (node (ref "U2") (pin "7") (pinfunction "A_7") (pintype "passive"))
      (node (ref "U6") (pin "9") (pinfunction "EMIT_9") (pintype "passive"))
    )
    (net (code "80") (name "R17") (class "Default")
      (node (ref "R17") (pin "2") (pinfunction "2_2") (pintype "passive"))
      (node (ref "U3") (pin "1") (pinfunction "A_1") (pintype "passive"))
      (node (ref "U7") (pin "15") (pinfunction "EMIT_15") (pintype "passive"))
    )
    (net (code "81") (name "R19") (class "Default")
      (node (ref "R19") (pin "2") (pinfunction "2_2") (pintype "passive"))
      (node (ref "U3") (pin "3") (pinfunction "A_3") (pintype "passive"))
      (node (ref "U7") (pin "13") (pinfunction "EMIT_13") (pintype "passive"))
    )
    (net (code "82") (name "R21") (class "Default")
      (node (ref "R21") (pin "2") (pinfunction "2_2") (pintype "passive"))
      (node (ref "U3") (pin "5") (pinfunction "A_5") (pintype "passive"))
      (node (ref "U7") (pin "11") (pinfunction "EMIT_11") (pintype "passive"))
    )
    (net (code "83") (name "R23") (class "Default")
      (node (ref "R23") (pin "2") (pinfunction "2_2") (pintype "passive"))
      (node (ref "U3") (pin "7") (pinfunction "A_7") (pintype "passive"))
      (node (ref "U7") (pin "9") (pinfunction "EMIT_9") (pintype "passive"))
    )
    (net (code "84") (name "R25") (class "Default")
      (node (ref "R25") (pin "2") (pinfunction "2_2") (pintype "passive"))
      (node (ref "U4") (pin "1") (pinfunction "A_1") (pintype "passive"))
      (node (ref "U8") (pin "15") (pinfunction "EMIT_15") (pintype "passive"))
    )
    (net (code "85") (name "R27") (class "Default")
      (node (ref "R27") (pin "2") (pinfunction "2_2") (pintype "passive"))
      (node (ref "U4") (pin "3") (pinfunction "A_3") (pintype "passive"))
      (node (ref "U8") (pin "13") (pinfunction "EMIT_13") (pintype "passive"))
    )
    (net (code "86") (name "R29") (class "Default")
      (node (ref "R29") (pin "2") (pinfunction "2_2") (pintype "passive"))
      (node (ref "U4") (pin "5") (pinfunction "A_5") (pintype "passive"))
      (node (ref "U8") (pin "11") (pinfunction "EMIT_11") (pintype "passive"))
    )
    (net (code "87") (name "R31") (class "Default")
      (node (ref "R31") (pin "2") (pinfunction "2_2") (pintype "passive"))
      (node (ref "U4") (pin "7") (pinfunction "A_7") (pintype "passive"))
      (node (ref "U8") (pin "9") (pinfunction "EMIT_9") (pintype "passive"))
    )
    (net (code "88") (name "unconnected-(JP1-Pad2)") (class "Default")
      (node (ref "JP1") (pin "2") (pinfunction "2_2") (pintype "passive"))
    )
    (net (code "89") (name "unconnected-(JP1-Pad4)") (class "Default")
      (node (ref "JP1") (pin "4") (pinfunction "4_4") (pintype "passive"))
    )
    (net (code "90") (name "unconnected-(JP1-Pad6)") (class "Default")
      (node (ref "JP1") (pin "6") (pinfunction "6_6") (pintype "passive"))
    )
    (net (code "91") (name "unconnected-(JP1-Pad8)") (class "Default")
      (node (ref "JP1") (pin "8") (pinfunction "8_8") (pintype "passive"))
    )
    (net (code "92") (name "unconnected-(JP1-Pad9)") (class "Default")
      (node (ref "JP1") (pin "9") (pinfunction "9_9") (pintype "passive"))
    )
    (net (code "93") (name "unconnected-(JP1-Pad10)") (class "Default")
      (node (ref "JP1") (pin "10") (pinfunction "10_10") (pintype "passive"))
    )
    (net (code "94") (name "unconnected-(JP1-Pad11)") (class "Default")
      (node (ref "JP1") (pin "11") (pinfunction "11_11") (pintype "passive"))
    )
    (net (code "95") (name "unconnected-(JP1-Pad12)") (class "Default")
      (node (ref "JP1") (pin "12") (pinfunction "12_12") (pintype "passive"))
    )
    (net (code "96") (name "unconnected-(JP1-Pad13)") (class "Default")
      (node (ref "JP1") (pin "13") (pinfunction "13_13") (pintype "passive"))
    )
    (net (code "97") (name "unconnected-(JP1-Pad14)") (class "Default")
      (node (ref "JP1") (pin "14") (pinfunction "14_14") (pintype "passive"))
    )
    (net (code "98") (name "unconnected-(JP1-Pad15)") (class "Default")
      (node (ref "JP1") (pin "15") (pinfunction "15_15") (pintype "passive"))
    )
    (net (code "99") (name "unconnected-(JP1-Pad16)") (class "Default")
      (node (ref "JP1") (pin "16") (pinfunction "16_16") (pintype "passive"))
    )
    (net (code "100") (name "unconnected-(JP1-Pad17)") (class "Default")
      (node (ref "JP1") (pin "17") (pinfunction "17_17") (pintype "passive"))
    )
    (net (code "101") (name "unconnected-(JP1-Pad18)") (class "Default")
      (node (ref "JP1") (pin "18") (pinfunction "18_18") (pintype "passive"))
    )
    (net (code "102") (name "unconnected-(JP1-Pad19)") (class "Default")
      (node (ref "JP1") (pin "19") (pinfunction "19_19") (pintype "passive"))
    )
    (net (code "103") (name "unconnected-(JP1-Pad20)") (class "Default")
      (node (ref "JP1") (pin "20") (pinfunction "20_20") (pintype "passive"))
    )
    (net (code "104") (name "unconnected-(JP1-Pad21)") (class "Default")
      (node (ref "JP1") (pin "21") (pinfunction "21_21") (pintype "passive"))
    )
    (net (code "105") (name "unconnected-(JP1-Pad22)") (class "Default")
      (node (ref "JP1") (pin "22") (pinfunction "22_22") (pintype "passive"))
    )
    (net (code "106") (name "unconnected-(JP1-Pad23)") (class "Default")
      (node (ref "JP1") (pin "23") (pinfunction "23_23") (pintype "passive"))
    )
    (net (code "107") (name "unconnected-(JP1-Pad24)") (class "Default")
      (node (ref "JP1") (pin "24") (pinfunction "24_24") (pintype "passive"))
    )
    (net (code "108") (name "unconnected-(JP1-Pad25)") (class "Default")
      (node (ref "JP1") (pin "25") (pinfunction "25_25") (pintype "passive"))
    )
    (net (code "109") (name "unconnected-(JP1-Pad26)") (class "Default")
      (node (ref "JP1") (pin "26") (pinfunction "26_26") (pintype "passive"))
    )
    (net (code "110") (name "unconnected-(JP1-Pad27)") (class "Default")
      (node (ref "JP1") (pin "27") (pinfunction "27_27") (pintype "passive"))
    )
    (net (code "111") (name "unconnected-(JP1-Pad28)") (class "Default")
      (node (ref "JP1") (pin "28") (pinfunction "28_28") (pintype "passive"))
    )
    (net (code "112") (name "unconnected-(JP1-Pad29)") (class "Default")
      (node (ref "JP1") (pin "29") (pinfunction "29_29") (pintype "passive"))
    )
    (net (code "113") (name "unconnected-(JP1-Pad30)") (class "Default")
      (node (ref "JP1") (pin "30") (pinfunction "30_30") (pintype "passive"))
    )
    (net (code "114") (name "unconnected-(JP1-Pad31)") (class "Default")
      (node (ref "JP1") (pin "31") (pinfunction "31_31") (pintype "passive"))
    )
    (net (code "115") (name "unconnected-(JP1-Pad32)") (class "Default")
      (node (ref "JP1") (pin "32") (pinfunction "32_32") (pintype "passive"))
    )
    (net (code "116") (name "unconnected-(JP1-Pad33)") (class "Default")
      (node (ref "JP1") (pin "33") (pinfunction "33_33") (pintype "passive"))
    )
    (net (code "117") (name "unconnected-(JP1-Pad34)") (class "Default")
      (node (ref "JP1") (pin "34") (pinfunction "34_34") (pintype "passive"))
    )
    (net (code "118") (name "unconnected-(JP1-Pad35)") (class "Default")
      (node (ref "JP1") (pin "35") (pinfunction "35_35") (pintype "passive"))
    )
    (net (code "119") (name "unconnected-(JP1-Pad36)") (class "Default")
      (node (ref "JP1") (pin "36") (pinfunction "36_36") (pintype "passive"))
    )
    (net (code "120") (name "unconnected-(JP1-Pad37)") (class "Default")
      (node (ref "JP1") (pin "37") (pinfunction "37_37") (pintype "passive"))
    )
    (net (code "121") (name "unconnected-(JP1-Pad38)") (class "Default")
      (node (ref "JP1") (pin "38") (pinfunction "38_38") (pintype "passive"))
    )
    (net (code "122") (name "unconnected-(JP1-Pad39)") (class "Default")
      (node (ref "JP1") (pin "39") (pinfunction "39_39") (pintype "passive"))
    )
    (net (code "123") (name "unconnected-(JP1-Pad40)") (class "Default")
      (node (ref "JP1") (pin "40") (pinfunction "40_40") (pintype "passive"))
    )
    (net (code "124") (name "unconnected-(JP1-Pad41)") (class "Default")
      (node (ref "JP1") (pin "41") (pinfunction "41_41") (pintype "passive"))
    )
    (net (code "125") (name "unconnected-(JP1-Pad42)") (class "Default")
      (node (ref "JP1") (pin "42") (pinfunction "42_42") (pintype "passive"))
    )
    (net (code "126") (name "unconnected-(JP1-Pad43)") (class "Default")
      (node (ref "JP1") (pin "43") (pinfunction "43_43") (pintype "passive"))
    )
    (net (code "127") (name "unconnected-(JP1-Pad44)") (class "Default")
      (node (ref "JP1") (pin "44") (pinfunction "44_44") (pintype "passive"))
    )
    (net (code "128") (name "unconnected-(JP1-Pad45)") (class "Default")
      (node (ref "JP1") (pin "45") (pinfunction "45_45") (pintype "passive"))
    )
    (net (code "129") (name "unconnected-(JP1-Pad46)") (class "Default")
      (node (ref "JP1") (pin "46") (pinfunction "46_46") (pintype "passive"))
    )
    (net (code "130") (name "unconnected-(JP1-Pad47)") (class "Default")
      (node (ref "JP1") (pin "47") (pinfunction "47_47") (pintype "passive"))
    )
    (net (code "131") (name "unconnected-(JP1-Pad48)") (class "Default")
      (node (ref "JP1") (pin "48") (pinfunction "48_48") (pintype "passive"))
    )
    (net (code "132") (name "unconnected-(JP2-Pad1)") (class "Default")
      (node (ref "JP2") (pin "1") (pinfunction "1_1") (pintype "passive"))
    )
    (net (code "133") (name "unconnected-(JP2-Pad2)") (class "Default")
      (node (ref "JP2") (pin "2") (pinfunction "2_2") (pintype "passive"))
    )
    (net (code "134") (name "unconnected-(JP2-Pad3)") (class "Default")
      (node (ref "JP2") (pin "3") (pinfunction "3_3") (pintype "passive"))
    )
    (net (code "135") (name "unconnected-(JP2-Pad4)") (class "Default")
      (node (ref "JP2") (pin "4") (pinfunction "4_4") (pintype "passive"))
    )
    (net (code "136") (name "unconnected-(JP2-Pad5)") (class "Default")
      (node (ref "JP2") (pin "5") (pinfunction "5_5") (pintype "passive"))
    )
    (net (code "137") (name "unconnected-(JP2-Pad6)") (class "Default")
      (node (ref "JP2") (pin "6") (pinfunction "6_6") (pintype "passive"))
    )
    (net (code "138") (name "unconnected-(JP2-Pad7)") (class "Default")
      (node (ref "JP2") (pin "7") (pinfunction "7_7") (pintype "passive"))
    )
    (net (code "139") (name "unconnected-(JP2-Pad8)") (class "Default")
      (node (ref "JP2") (pin "8") (pinfunction "8_8") (pintype "passive"))
    )
    (net (code "140") (name "unconnected-(JP2-Pad9)") (class "Default")
      (node (ref "JP2") (pin "9") (pinfunction "9_9") (pintype "passive"))
    )
    (net (code "141") (name "unconnected-(JP2-Pad10)") (class "Default")
      (node (ref "JP2") (pin "10") (pinfunction "10_10") (pintype "passive"))
    )
    (net (code "142") (name "unconnected-(JP2-Pad11)") (class "Default")
      (node (ref "JP2") (pin "11") (pinfunction "11_11") (pintype "passive"))
    )
    (net (code "143") (name "unconnected-(JP2-Pad12)") (class "Default")
      (node (ref "JP2") (pin "12") (pinfunction "12_12") (pintype "passive"))
    )
    (net (code "144") (name "unconnected-(JP2-Pad13)") (class "Default")
      (node (ref "JP2") (pin "13") (pinfunction "13_13") (pintype "passive"))
    )
    (net (code "145") (name "unconnected-(JP2-Pad14)") (class "Default")
      (node (ref "JP2") (pin "14") (pinfunction "14_14") (pintype "passive"))
    )
    (net (code "146") (name "unconnected-(JP2-Pad15)") (class "Default")
      (node (ref "JP2") (pin "15") (pinfunction "15_15") (pintype "passive"))
    )
    (net (code "147") (name "unconnected-(JP2-Pad16)") (class "Default")
      (node (ref "JP2") (pin "16") (pinfunction "16_16") (pintype "passive"))
    )
    (net (code "148") (name "unconnected-(JP2-Pad17)") (class "Default")
      (node (ref "JP2") (pin "17") (pinfunction "17_17") (pintype "passive"))
    )
    (net (code "149") (name "unconnected-(JP2-Pad18)") (class "Default")
      (node (ref "JP2") (pin "18") (pinfunction "18_18") (pintype "passive"))
    )
    (net (code "150") (name "unconnected-(JP2-Pad19)") (class "Default")
      (node (ref "JP2") (pin "19") (pinfunction "19_19") (pintype "passive"))
    )
    (net (code "151") (name "unconnected-(JP2-Pad20)") (class "Default")
      (node (ref "JP2") (pin "20") (pinfunction "20_20") (pintype "passive"))
    )
    (net (code "152") (name "unconnected-(JP2-Pad21)") (class "Default")
      (node (ref "JP2") (pin "21") (pinfunction "21_21") (pintype "passive"))
    )
    (net (code "153") (name "unconnected-(JP2-Pad22)") (class "Default")
      (node (ref "JP2") (pin "22") (pinfunction "22_22") (pintype "passive"))
    )
    (net (code "154") (name "unconnected-(JP2-Pad23)") (class "Default")
      (node (ref "JP2") (pin "23") (pinfunction "23_23") (pintype "passive"))
    )
    (net (code "155") (name "unconnected-(JP2-Pad24)") (class "Default")
      (node (ref "JP2") (pin "24") (pinfunction "24_24") (pintype "passive"))
    )
    (net (code "156") (name "unconnected-(JP2-Pad25)") (class "Default")
      (node (ref "JP2") (pin "25") (pinfunction "25_25") (pintype "passive"))
    )
    (net (code "157") (name "unconnected-(JP2-Pad26)") (class "Default")
      (node (ref "JP2") (pin "26") (pinfunction "26_26") (pintype "passive"))
    )
    (net (code "158") (name "unconnected-(JP2-Pad27)") (class "Default")
      (node (ref "JP2") (pin "27") (pinfunction "27_27") (pintype "passive"))
    )
    (net (code "159") (name "unconnected-(JP2-Pad28)") (class "Default")
      (node (ref "JP2") (pin "28") (pinfunction "28_28") (pintype "passive"))
    )
    (net (code "160") (name "unconnected-(JP2-Pad29)") (class "Default")
      (node (ref "JP2") (pin "29") (pinfunction "29_29") (pintype "passive"))
    )
    (net (code "161") (name "unconnected-(JP2-Pad30)") (class "Default")
      (node (ref "JP2") (pin "30") (pinfunction "30_30") (pintype "passive"))
    )
    (net (code "162") (name "unconnected-(JP2-Pad31)") (class "Default")
      (node (ref "JP2") (pin "31") (pinfunction "31_31") (pintype "passive"))
    )
    (net (code "163") (name "unconnected-(JP2-Pad32)") (class "Default")
      (node (ref "JP2") (pin "32") (pinfunction "32_32") (pintype "passive"))
    )
    (net (code "164") (name "unconnected-(JP2-Pad33)") (class "Default")
      (node (ref "JP2") (pin "33") (pinfunction "33_33") (pintype "passive"))
    )
    (net (code "165") (name "unconnected-(JP2-Pad34)") (class "Default")
      (node (ref "JP2") (pin "34") (pinfunction "34_34") (pintype "passive"))
    )
    (net (code "166") (name "unconnected-(JP2-Pad35)") (class "Default")
      (node (ref "JP2") (pin "35") (pinfunction "35_35") (pintype "passive"))
    )
    (net (code "167") (name "unconnected-(JP2-Pad36)") (class "Default")
      (node (ref "JP2") (pin "36") (pinfunction "36_36") (pintype "passive"))
    )
    (net (code "168") (name "unconnected-(JP2-Pad37)") (class "Default")
      (node (ref "JP2") (pin "37") (pinfunction "37_37") (pintype "passive"))
    )
    (net (code "169") (name "unconnected-(JP2-Pad38)") (class "Default")
      (node (ref "JP2") (pin "38") (pinfunction "38_38") (pintype "passive"))
    )
    (net (code "170") (name "unconnected-(JP2-Pad39)") (class "Default")
      (node (ref "JP2") (pin "39") (pinfunction "39_39") (pintype "passive"))
    )
    (net (code "171") (name "unconnected-(JP2-Pad40)") (class "Default")
      (node (ref "JP2") (pin "40") (pinfunction "40_40") (pintype "passive"))
    )
    (net (code "172") (name "unconnected-(JP2-Pad41)") (class "Default")
      (node (ref "JP2") (pin "41") (pinfunction "41_41") (pintype "passive"))
    )
    (net (code "173") (name "unconnected-(JP2-Pad42)") (class "Default")
      (node (ref "JP2") (pin "42") (pinfunction "42_42") (pintype "passive"))
    )
    (net (code "174") (name "unconnected-(JP2-Pad43)") (class "Default")
      (node (ref "JP2") (pin "43") (pinfunction "43_43") (pintype "passive"))
    )
    (net (code "175") (name "unconnected-(JP2-Pad44)") (class "Default")
      (node (ref "JP2") (pin "44") (pinfunction "44_44") (pintype "passive"))
    )
    (net (code "176") (name "unconnected-(JP2-Pad45)") (class "Default")
      (node (ref "JP2") (pin "45") (pinfunction "45_45") (pintype "passive"))
    )
    (net (code "177") (name "unconnected-(JP2-Pad46)") (class "Default")
      (node (ref "JP2") (pin "46") (pinfunction "46_46") (pintype "passive"))
    )
    (net (code "178") (name "unconnected-(JP2-Pad47)") (class "Default")
      (node (ref "JP2") (pin "47") (pinfunction "47_47") (pintype "passive"))
    )
    (net (code "179") (name "unconnected-(JP2-Pad48)") (class "Default")
      (node (ref "JP2") (pin "48") (pinfunction "48_48") (pintype "passive"))
    )
    (net (code "180") (name "unconnected-(JP3-Pad1)") (class "Default")
      (node (ref "JP3") (pin "1") (pinfunction "1_1") (pintype "passive"))
    )
    (net (code "181") (name "unconnected-(JP3-Pad2)") (class "Default")
      (node (ref "JP3") (pin "2") (pinfunction "2_2") (pintype "passive"))
    )
    (net (code "182") (name "unconnected-(JP3-Pad3)") (class "Default")
      (node (ref "JP3") (pin "3") (pinfunction "3_3") (pintype "passive"))
    )
    (net (code "183") (name "unconnected-(JP3-Pad4)") (class "Default")
      (node (ref "JP3") (pin "4") (pinfunction "4_4") (pintype "passive"))
    )
    (net (code "184") (name "unconnected-(JP3-Pad5)") (class "Default")
      (node (ref "JP3") (pin "5") (pinfunction "5_5") (pintype "passive"))
    )
    (net (code "185") (name "unconnected-(JP3-Pad6)") (class "Default")
      (node (ref "JP3") (pin "6") (pinfunction "6_6") (pintype "passive"))
    )
    (net (code "186") (name "unconnected-(JP3-Pad7)") (class "Default")
      (node (ref "JP3") (pin "7") (pinfunction "7_7") (pintype "passive"))
    )
    (net (code "187") (name "unconnected-(JP3-Pad8)") (class "Default")
      (node (ref "JP3") (pin "8") (pinfunction "8_8") (pintype "passive"))
    )
    (net (code "188") (name "unconnected-(JP3-Pad9)") (class "Default")
      (node (ref "JP3") (pin "9") (pinfunction "9_9") (pintype "passive"))
    )
    (net (code "189") (name "unconnected-(JP3-Pad10)") (class "Default")
      (node (ref "JP3") (pin "10") (pinfunction "10_10") (pintype "passive"))
    )
    (net (code "190") (name "unconnected-(JP3-Pad11)") (class "Default")
      (node (ref "JP3") (pin "11") (pinfunction "11_11") (pintype "passive"))
    )
    (net (code "191") (name "unconnected-(JP3-Pad12)") (class "Default")
      (node (ref "JP3") (pin "12") (pinfunction "12_12") (pintype "passive"))
    )
    (net (code "192") (name "unconnected-(JP3-Pad13)") (class "Default")
      (node (ref "JP3") (pin "13") (pinfunction "13_13") (pintype "passive"))
    )
    (net (code "193") (name "unconnected-(JP3-Pad14)") (class "Default")
      (node (ref "JP3") (pin "14") (pinfunction "14_14") (pintype "passive"))
    )
    (net (code "194") (name "unconnected-(JP3-Pad15)") (class "Default")
      (node (ref "JP3") (pin "15") (pinfunction "15_15") (pintype "passive"))
    )
    (net (code "195") (name "unconnected-(JP3-Pad16)") (class "Default")
      (node (ref "JP3") (pin "16") (pinfunction "16_16") (pintype "passive"))
    )
    (net (code "196") (name "unconnected-(JP3-Pad17)") (class "Default")
      (node (ref "JP3") (pin "17") (pinfunction "17_17") (pintype "passive"))
    )
    (net (code "197") (name "unconnected-(JP3-Pad18)") (class "Default")
      (node (ref "JP3") (pin "18") (pinfunction "18_18") (pintype "passive"))
    )
    (net (code "198") (name "unconnected-(JP3-Pad19)") (class "Default")
      (node (ref "JP3") (pin "19") (pinfunction "19_19") (pintype "passive"))
    )
    (net (code "199") (name "unconnected-(JP3-Pad20)") (class "Default")
      (node (ref "JP3") (pin "20") (pinfunction "20_20") (pintype "passive"))
    )
    (net (code "200") (name "unconnected-(JP3-Pad21)") (class "Default")
      (node (ref "JP3") (pin "21") (pinfunction "21_21") (pintype "passive"))
    )
    (net (code "201") (name "unconnected-(JP3-Pad22)") (class "Default")
      (node (ref "JP3") (pin "22") (pinfunction "22_22") (pintype "passive"))
    )
    (net (code "202") (name "unconnected-(JP3-Pad23)") (class "Default")
      (node (ref "JP3") (pin "23") (pinfunction "23_23") (pintype "passive"))
    )
    (net (code "203") (name "unconnected-(JP3-Pad24)") (class "Default")
      (node (ref "JP3") (pin "24") (pinfunction "24_24") (pintype "passive"))
    )
    (net (code "204") (name "unconnected-(JP3-Pad25)") (class "Default")
      (node (ref "JP3") (pin "25") (pinfunction "25_25") (pintype "passive"))
    )
    (net (code "205") (name "unconnected-(JP3-Pad26)") (class "Default")
      (node (ref "JP3") (pin "26") (pinfunction "26_26") (pintype "passive"))
    )
    (net (code "206") (name "unconnected-(JP3-Pad27)") (class "Default")
      (node (ref "JP3") (pin "27") (pinfunction "27_27") (pintype "passive"))
    )
    (net (code "207") (name "unconnected-(JP3-Pad28)") (class "Default")
      (node (ref "JP3") (pin "28") (pinfunction "28_28") (pintype "passive"))
    )
    (net (code "208") (name "unconnected-(JP3-Pad29)") (class "Default")
      (node (ref "JP3") (pin "29") (pinfunction "29_29") (pintype "passive"))
    )
    (net (code "209") (name "unconnected-(JP3-Pad30)") (class "Default")
      (node (ref "JP3") (pin "30") (pinfunction "30_30") (pintype "passive"))
    )
    (net (code "210") (name "unconnected-(JP3-Pad31)") (class "Default")
      (node (ref "JP3") (pin "31") (pinfunction "31_31") (pintype "passive"))
    )
    (net (code "211") (name "unconnected-(JP3-Pad32)") (class "Default")
      (node (ref "JP3") (pin "32") (pinfunction "32_32") (pintype "passive"))
    )
    (net (code "212") (name "unconnected-(JP3-Pad33)") (class "Default")
      (node (ref "JP3") (pin "33") (pinfunction "33_33") (pintype "passive"))
    )
    (net (code "213") (name "unconnected-(JP3-Pad34)") (class "Default")
      (node (ref "JP3") (pin "34") (pinfunction "34_34") (pintype "passive"))
    )
    (net (code "214") (name "unconnected-(JP3-Pad35)") (class "Default")
      (node (ref "JP3") (pin "35") (pinfunction "35_35") (pintype "passive"))
    )
    (net (code "215") (name "unconnected-(JP3-Pad36)") (class "Default")
      (node (ref "JP3") (pin "36") (pinfunction "36_36") (pintype "passive"))
    )
    (net (code "216") (name "unconnected-(JP3-Pad37)") (class "Default")
      (node (ref "JP3") (pin "37") (pinfunction "37_37") (pintype "passive"))
    )
    (net (code "217") (name "unconnected-(JP3-Pad38)") (class "Default")
      (node (ref "JP3") (pin "38") (pinfunction "38_38") (pintype "passive"))
    )
    (net (code "218") (name "unconnected-(JP3-Pad39)") (class "Default")
      (node (ref "JP3") (pin "39") (pinfunction "39_39") (pintype "passive"))
    )
    (net (code "219") (name "unconnected-(JP3-Pad40)") (class "Default")
      (node (ref "JP3") (pin "40") (pinfunction "40_40") (pintype "passive"))
    )
    (net (code "220") (name "unconnected-(JP3-Pad41)") (class "Default")
      (node (ref "JP3") (pin "41") (pinfunction "41_41") (pintype "passive"))
    )
    (net (code "221") (name "unconnected-(JP3-Pad42)") (class "Default")
      (node (ref "JP3") (pin "42") (pinfunction "42_42") (pintype "passive"))
    )
    (net (code "222") (name "unconnected-(JP3-Pad43)") (class "Default")
      (node (ref "JP3") (pin "43") (pinfunction "43_43") (pintype "passive"))
    )
    (net (code "223") (name "unconnected-(JP3-Pad44)") (class "Default")
      (node (ref "JP3") (pin "44") (pinfunction "44_44") (pintype "passive"))
    )
    (net (code "224") (name "unconnected-(JP3-Pad45)") (class "Default")
      (node (ref "JP3") (pin "45") (pinfunction "45_45") (pintype "passive"))
    )
    (net (code "225") (name "unconnected-(JP3-Pad46)") (class "Default")
      (node (ref "JP3") (pin "46") (pinfunction "46_46") (pintype "passive"))
    )
    (net (code "226") (name "unconnected-(JP3-Pad47)") (class "Default")
      (node (ref "JP3") (pin "47") (pinfunction "47_47") (pintype "passive"))
    )
    (net (code "227") (name "unconnected-(JP3-Pad48)") (class "Default")
      (node (ref "JP3") (pin "48") (pinfunction "48_48") (pintype "passive"))
    )
    (net (code "228") (name "unconnected-(JP4-Pad1)") (class "Default")
      (node (ref "JP4") (pin "1") (pinfunction "1_1") (pintype "passive"))
    )
    (net (code "229") (name "unconnected-(JP4-Pad2)") (class "Default")
      (node (ref "JP4") (pin "2") (pinfunction "2_2") (pintype "passive"))
    )
    (net (code "230") (name "unconnected-(JP4-Pad3)") (class "Default")
      (node (ref "JP4") (pin "3") (pinfunction "3_3") (pintype "passive"))
    )
    (net (code "231") (name "unconnected-(JP4-Pad4)") (class "Default")
      (node (ref "JP4") (pin "4") (pinfunction "4_4") (pintype "passive"))
    )
    (net (code "232") (name "unconnected-(JP4-Pad5)") (class "Default")
      (node (ref "JP4") (pin "5") (pinfunction "5_5") (pintype "passive"))
    )
    (net (code "233") (name "unconnected-(JP4-Pad6)") (class "Default")
      (node (ref "JP4") (pin "6") (pinfunction "6_6") (pintype "passive"))
    )
    (net (code "234") (name "unconnected-(JP4-Pad7)") (class "Default")
      (node (ref "JP4") (pin "7") (pinfunction "7_7") (pintype "passive"))
    )
    (net (code "235") (name "unconnected-(JP4-Pad8)") (class "Default")
      (node (ref "JP4") (pin "8") (pinfunction "8_8") (pintype "passive"))
    )
    (net (code "236") (name "unconnected-(JP4-Pad9)") (class "Default")
      (node (ref "JP4") (pin "9") (pinfunction "9_9") (pintype "passive"))
    )
    (net (code "237") (name "unconnected-(JP4-Pad10)") (class "Default")
      (node (ref "JP4") (pin "10") (pinfunction "10_10") (pintype "passive"))
    )
    (net (code "238") (name "unconnected-(JP4-Pad11)") (class "Default")
      (node (ref "JP4") (pin "11") (pinfunction "11_11") (pintype "passive"))
    )
    (net (code "239") (name "unconnected-(JP4-Pad12)") (class "Default")
      (node (ref "JP4") (pin "12") (pinfunction "12_12") (pintype "passive"))
    )
    (net (code "240") (name "unconnected-(JP4-Pad13)") (class "Default")
      (node (ref "JP4") (pin "13") (pinfunction "13_13") (pintype "passive"))
    )
    (net (code "241") (name "unconnected-(JP4-Pad14)") (class "Default")
      (node (ref "JP4") (pin "14") (pinfunction "14_14") (pintype "passive"))
    )
    (net (code "242") (name "unconnected-(JP4-Pad15)") (class "Default")
      (node (ref "JP4") (pin "15") (pinfunction "15_15") (pintype "passive"))
    )
    (net (code "243") (name "unconnected-(JP4-Pad16)") (class "Default")
      (node (ref "JP4") (pin "16") (pinfunction "16_16") (pintype "passive"))
    )
    (net (code "244") (name "unconnected-(JP4-Pad17)") (class "Default")
      (node (ref "JP4") (pin "17") (pinfunction "17_17") (pintype "passive"))
    )
    (net (code "245") (name "unconnected-(JP4-Pad18)") (class "Default")
      (node (ref "JP4") (pin "18") (pinfunction "18_18") (pintype "passive"))
    )
    (net (code "246") (name "unconnected-(JP4-Pad19)") (class "Default")
      (node (ref "JP4") (pin "19") (pinfunction "19_19") (pintype "passive"))
    )
    (net (code "247") (name "unconnected-(JP4-Pad20)") (class "Default")
      (node (ref "JP4") (pin "20") (pinfunction "20_20") (pintype "passive"))
    )
    (net (code "248") (name "unconnected-(JP4-Pad21)") (class "Default")
      (node (ref "JP4") (pin "21") (pinfunction "21_21") (pintype "passive"))
    )
    (net (code "249") (name "unconnected-(JP4-Pad22)") (class "Default")
      (node (ref "JP4") (pin "22") (pinfunction "22_22") (pintype "passive"))
    )
    (net (code "250") (name "unconnected-(JP4-Pad23)") (class "Default")
      (node (ref "JP4") (pin "23") (pinfunction "23_23") (pintype "passive"))
    )
    (net (code "251") (name "unconnected-(JP4-Pad24)") (class "Default")
      (node (ref "JP4") (pin "24") (pinfunction "24_24") (pintype "passive"))
    )
    (net (code "252") (name "unconnected-(JP4-Pad25)") (class "Default")
      (node (ref "JP4") (pin "25") (pinfunction "25_25") (pintype "passive"))
    )
    (net (code "253") (name "unconnected-(JP4-Pad26)") (class "Default")
      (node (ref "JP4") (pin "26") (pinfunction "26_26") (pintype "passive"))
    )
    (net (code "254") (name "unconnected-(JP4-Pad27)") (class "Default")
      (node (ref "JP4") (pin "27") (pinfunction "27_27") (pintype "passive"))
    )
    (net (code "255") (name "unconnected-(JP4-Pad28)") (class "Default")
      (node (ref "JP4") (pin "28") (pinfunction "28_28") (pintype "passive"))
    )
    (net (code "256") (name "unconnected-(JP4-Pad29)") (class "Default")
      (node (ref "JP4") (pin "29") (pinfunction "29_29") (pintype "passive"))
    )
    (net (code "257") (name "unconnected-(JP4-Pad30)") (class "Default")
      (node (ref "JP4") (pin "30") (pinfunction "30_30") (pintype "passive"))
    )
    (net (code "258") (name "unconnected-(JP4-Pad31)") (class "Default")
      (node (ref "JP4") (pin "31") (pinfunction "31_31") (pintype "passive"))
    )
    (net (code "259") (name "unconnected-(JP4-Pad32)") (class "Default")
      (node (ref "JP4") (pin "32") (pinfunction "32_32") (pintype "passive"))
    )
    (net (code "260") (name "unconnected-(JP4-Pad33)") (class "Default")
      (node (ref "JP4") (pin "33") (pinfunction "33_33") (pintype "passive"))
    )
    (net (code "261") (name "unconnected-(JP4-Pad34)") (class "Default")
      (node (ref "JP4") (pin "34") (pinfunction "34_34") (pintype "passive"))
    )
    (net (code "262") (name "unconnected-(JP4-Pad35)") (class "Default")
      (node (ref "JP4") (pin "35") (pinfunction "35_35") (pintype "passive"))
    )
    (net (code "263") (name "unconnected-(JP4-Pad36)") (class "Default")
      (node (ref "JP4") (pin "36") (pinfunction "36_36") (pintype "passive"))
    )
    (net (code "264") (name "unconnected-(JP4-Pad37)") (class "Default")
      (node (ref "JP4") (pin "37") (pinfunction "37_37") (pintype "passive"))
    )
    (net (code "265") (name "unconnected-(JP4-Pad38)") (class "Default")
      (node (ref "JP4") (pin "38") (pinfunction "38_38") (pintype "passive"))
    )
    (net (code "266") (name "unconnected-(JP4-Pad39)") (class "Default")
      (node (ref "JP4") (pin "39") (pinfunction "39_39") (pintype "passive"))
    )
    (net (code "267") (name "unconnected-(JP4-Pad40)") (class "Default")
      (node (ref "JP4") (pin "40") (pinfunction "40_40") (pintype "passive"))
    )
    (net (code "268") (name "unconnected-(JP4-Pad41)") (class "Default")
      (node (ref "JP4") (pin "41") (pinfunction "41_41") (pintype "passive"))
    )
    (net (code "269") (name "unconnected-(JP4-Pad42)") (class "Default")
      (node (ref "JP4") (pin "42") (pinfunction "42_42") (pintype "passive"))
    )
    (net (code "270") (name "unconnected-(JP4-Pad43)") (class "Default")
      (node (ref "JP4") (pin "43") (pinfunction "43_43") (pintype "passive"))
    )
    (net (code "271") (name "unconnected-(JP4-Pad44)") (class "Default")
      (node (ref "JP4") (pin "44") (pinfunction "44_44") (pintype "passive"))
    )
    (net (code "272") (name "unconnected-(JP4-Pad45)") (class "Default")
      (node (ref "JP4") (pin "45") (pinfunction "45_45") (pintype "passive"))
    )
    (net (code "273") (name "unconnected-(JP4-Pad46)") (class "Default")
      (node (ref "JP4") (pin "46") (pinfunction "46_46") (pintype "passive"))
    )
    (net (code "274") (name "unconnected-(JP4-Pad47)") (class "Default")
      (node (ref "JP4") (pin "47") (pinfunction "47_47") (pintype "passive"))
    )
    (net (code "275") (name "unconnected-(JP4-Pad48)") (class "Default")
      (node (ref "JP4") (pin "48") (pinfunction "48_48") (pintype "passive"))
    )
    (net (code "276") (name "unconnected-(JP5-Pad1)") (class "Default")
      (node (ref "JP5") (pin "1") (pinfunction "1_1") (pintype "passive"))
    )
    (net (code "277") (name "unconnected-(JP5-Pad2)") (class "Default")
      (node (ref "JP5") (pin "2") (pinfunction "2_2") (pintype "passive"))
    )
    (net (code "278") (name "unconnected-(JP5-Pad3)") (class "Default")
      (node (ref "JP5") (pin "3") (pinfunction "3_3") (pintype "passive"))
    )
    (net (code "279") (name "unconnected-(JP5-Pad4)") (class "Default")
      (node (ref "JP5") (pin "4") (pinfunction "4_4") (pintype "passive"))
    )
    (net (code "280") (name "unconnected-(JP5-Pad5)") (class "Default")
      (node (ref "JP5") (pin "5") (pinfunction "5_5") (pintype "passive"))
    )
    (net (code "281") (name "unconnected-(JP5-Pad6)") (class "Default")
      (node (ref "JP5") (pin "6") (pinfunction "6_6") (pintype "passive"))
    )
    (net (code "282") (name "unconnected-(JP5-Pad7)") (class "Default")
      (node (ref "JP5") (pin "7") (pinfunction "7_7") (pintype "passive"))
    )
    (net (code "283") (name "unconnected-(JP5-Pad8)") (class "Default")
      (node (ref "JP5") (pin "8") (pinfunction "8_8") (pintype "passive"))
    )
    (net (code "284") (name "unconnected-(JP5-Pad9)") (class "Default")
      (node (ref "JP5") (pin "9") (pinfunction "9_9") (pintype "passive"))
    )
    (net (code "285") (name "unconnected-(JP5-Pad10)") (class "Default")
      (node (ref "JP5") (pin "10") (pinfunction "10_10") (pintype "passive"))
    )
    (net (code "286") (name "unconnected-(JP5-Pad11)") (class "Default")
      (node (ref "JP5") (pin "11") (pinfunction "11_11") (pintype "passive"))
    )
    (net (code "287") (name "unconnected-(JP5-Pad12)") (class "Default")
      (node (ref "JP5") (pin "12") (pinfunction "12_12") (pintype "passive"))
    )
    (net (code "288") (name "unconnected-(JP5-Pad13)") (class "Default")
      (node (ref "JP5") (pin "13") (pinfunction "13_13") (pintype "passive"))
    )
    (net (code "289") (name "unconnected-(JP5-Pad14)") (class "Default")
      (node (ref "JP5") (pin "14") (pinfunction "14_14") (pintype "passive"))
    )
    (net (code "290") (name "unconnected-(JP5-Pad15)") (class "Default")
      (node (ref "JP5") (pin "15") (pinfunction "15_15") (pintype "passive"))
    )
    (net (code "291") (name "unconnected-(JP5-Pad16)") (class "Default")
      (node (ref "JP5") (pin "16") (pinfunction "16_16") (pintype "passive"))
    )
    (net (code "292") (name "unconnected-(JP5-Pad17)") (class "Default")
      (node (ref "JP5") (pin "17") (pinfunction "17_17") (pintype "passive"))
    )
    (net (code "293") (name "unconnected-(JP5-Pad18)") (class "Default")
      (node (ref "JP5") (pin "18") (pinfunction "18_18") (pintype "passive"))
    )
    (net (code "294") (name "unconnected-(JP5-Pad19)") (class "Default")
      (node (ref "JP5") (pin "19") (pinfunction "19_19") (pintype "passive"))
    )
    (net (code "295") (name "unconnected-(JP5-Pad20)") (class "Default")
      (node (ref "JP5") (pin "20") (pinfunction "20_20") (pintype "passive"))
    )
    (net (code "296") (name "unconnected-(JP5-Pad21)") (class "Default")
      (node (ref "JP5") (pin "21") (pinfunction "21_21") (pintype "passive"))
    )
    (net (code "297") (name "unconnected-(JP5-Pad22)") (class "Default")
      (node (ref "JP5") (pin "22") (pinfunction "22_22") (pintype "passive"))
    )
    (net (code "298") (name "unconnected-(JP5-Pad23)") (class "Default")
      (node (ref "JP5") (pin "23") (pinfunction "23_23") (pintype "passive"))
    )
    (net (code "299") (name "unconnected-(JP5-Pad24)") (class "Default")
      (node (ref "JP5") (pin "24") (pinfunction "24_24") (pintype "passive"))
    )
    (net (code "300") (name "unconnected-(JP5-Pad25)") (class "Default")
      (node (ref "JP5") (pin "25") (pinfunction "25_25") (pintype "passive"))
    )
    (net (code "301") (name "unconnected-(JP5-Pad26)") (class "Default")
      (node (ref "JP5") (pin "26") (pinfunction "26_26") (pintype "passive"))
    )
    (net (code "302") (name "unconnected-(JP5-Pad27)") (class "Default")
      (node (ref "JP5") (pin "27") (pinfunction "27_27") (pintype "passive"))
    )
    (net (code "303") (name "unconnected-(JP5-Pad28)") (class "Default")
      (node (ref "JP5") (pin "28") (pinfunction "28_28") (pintype "passive"))
    )
    (net (code "304") (name "unconnected-(JP5-Pad29)") (class "Default")
      (node (ref "JP5") (pin "29") (pinfunction "29_29") (pintype "passive"))
    )
    (net (code "305") (name "unconnected-(JP5-Pad30)") (class "Default")
      (node (ref "JP5") (pin "30") (pinfunction "30_30") (pintype "passive"))
    )
    (net (code "306") (name "unconnected-(JP5-Pad31)") (class "Default")
      (node (ref "JP5") (pin "31") (pinfunction "31_31") (pintype "passive"))
    )
    (net (code "307") (name "unconnected-(JP5-Pad32)") (class "Default")
      (node (ref "JP5") (pin "32") (pinfunction "32_32") (pintype "passive"))
    )
    (net (code "308") (name "unconnected-(JP5-Pad33)") (class "Default")
      (node (ref "JP5") (pin "33") (pinfunction "33_33") (pintype "passive"))
    )
    (net (code "309") (name "unconnected-(JP5-Pad34)") (class "Default")
      (node (ref "JP5") (pin "34") (pinfunction "34_34") (pintype "passive"))
    )
    (net (code "310") (name "unconnected-(JP5-Pad35)") (class "Default")
      (node (ref "JP5") (pin "35") (pinfunction "35_35") (pintype "passive"))
    )
    (net (code "311") (name "unconnected-(JP5-Pad36)") (class "Default")
      (node (ref "JP5") (pin "36") (pinfunction "36_36") (pintype "passive"))
    )
    (net (code "312") (name "unconnected-(JP5-Pad37)") (class "Default")
      (node (ref "JP5") (pin "37") (pinfunction "37_37") (pintype "passive"))
    )
    (net (code "313") (name "unconnected-(JP5-Pad38)") (class "Default")
      (node (ref "JP5") (pin "38") (pinfunction "38_38") (pintype "passive"))
    )
    (net (code "314") (name "unconnected-(JP5-Pad39)") (class "Default")
      (node (ref "JP5") (pin "39") (pinfunction "39_39") (pintype "passive"))
    )
    (net (code "315") (name "unconnected-(JP5-Pad40)") (class "Default")
      (node (ref "JP5") (pin "40") (pinfunction "40_40") (pintype "passive"))
    )
    (net (code "316") (name "unconnected-(JP5-Pad41)") (class "Default")
      (node (ref "JP5") (pin "41") (pinfunction "41_41") (pintype "passive"))
    )
    (net (code "317") (name "unconnected-(JP5-Pad42)") (class "Default")
      (node (ref "JP5") (pin "42") (pinfunction "42_42") (pintype "passive"))
    )
    (net (code "318") (name "unconnected-(JP5-Pad43)") (class "Default")
      (node (ref "JP5") (pin "43") (pinfunction "43_43") (pintype "passive"))
    )
    (net (code "319") (name "unconnected-(JP5-Pad44)") (class "Default")
      (node (ref "JP5") (pin "44") (pinfunction "44_44") (pintype "passive"))
    )
    (net (code "320") (name "unconnected-(JP5-Pad45)") (class "Default")
      (node (ref "JP5") (pin "45") (pinfunction "45_45") (pintype "passive"))
    )
    (net (code "321") (name "unconnected-(JP5-Pad46)") (class "Default")
      (node (ref "JP5") (pin "46") (pinfunction "46_46") (pintype "passive"))
    )
    (net (code "322") (name "unconnected-(JP5-Pad47)") (class "Default")
      (node (ref "JP5") (pin "47") (pinfunction "47_47") (pintype "passive"))
    )
    (net (code "323") (name "unconnected-(JP5-Pad48)") (class "Default")
      (node (ref "JP5") (pin "48") (pinfunction "48_48") (pintype "passive"))
    )
    (net (code "324") (name "unconnected-(JP6-Pad1)") (class "Default")
      (node (ref "JP6") (pin "1") (pinfunction "1_1") (pintype "passive"))
    )
    (net (code "325") (name "unconnected-(JP6-Pad3)") (class "Default")
      (node (ref "JP6") (pin "3") (pinfunction "3_3") (pintype "passive"))
    )
    (net (code "326") (name "unconnected-(JP6-Pad5)") (class "Default")
      (node (ref "JP6") (pin "5") (pinfunction "5_5") (pintype "passive"))
    )
    (net (code "327") (name "unconnected-(JP6-Pad7)") (class "Default")
      (node (ref "JP6") (pin "7") (pinfunction "7_7") (pintype "passive"))
    )
    (net (code "328") (name "unconnected-(JP6-Pad9)") (class "Default")
      (node (ref "JP6") (pin "9") (pinfunction "9_9") (pintype "passive"))
    )
    (net (code "329") (name "unconnected-(JP6-Pad10)") (class "Default")
      (node (ref "JP6") (pin "10") (pinfunction "10_10") (pintype "passive"))
    )
    (net (code "330") (name "unconnected-(JP6-Pad11)") (class "Default")
      (node (ref "JP6") (pin "11") (pinfunction "11_11") (pintype "passive"))
    )
    (net (code "331") (name "unconnected-(JP6-Pad12)") (class "Default")
      (node (ref "JP6") (pin "12") (pinfunction "12_12") (pintype "passive"))
    )
    (net (code "332") (name "unconnected-(JP6-Pad13)") (class "Default")
      (node (ref "JP6") (pin "13") (pinfunction "13_13") (pintype "passive"))
    )
    (net (code "333") (name "unconnected-(JP6-Pad14)") (class "Default")
      (node (ref "JP6") (pin "14") (pinfunction "14_14") (pintype "passive"))
    )
    (net (code "334") (name "unconnected-(JP6-Pad15)") (class "Default")
      (node (ref "JP6") (pin "15") (pinfunction "15_15") (pintype "passive"))
    )
    (net (code "335") (name "unconnected-(JP6-Pad16)") (class "Default")
      (node (ref "JP6") (pin "16") (pinfunction "16_16") (pintype "passive"))
    )
    (net (code "336") (name "unconnected-(JP6-Pad17)") (class "Default")
      (node (ref "JP6") (pin "17") (pinfunction "17_17") (pintype "passive"))
    )
    (net (code "337") (name "unconnected-(JP6-Pad18)") (class "Default")
      (node (ref "JP6") (pin "18") (pinfunction "18_18") (pintype "passive"))
    )
    (net (code "338") (name "unconnected-(JP6-Pad19)") (class "Default")
      (node (ref "JP6") (pin "19") (pinfunction "19_19") (pintype "passive"))
    )
    (net (code "339") (name "unconnected-(JP6-Pad20)") (class "Default")
      (node (ref "JP6") (pin "20") (pinfunction "20_20") (pintype "passive"))
    )
    (net (code "340") (name "unconnected-(JP6-Pad21)") (class "Default")
      (node (ref "JP6") (pin "21") (pinfunction "21_21") (pintype "passive"))
    )
    (net (code "341") (name "unconnected-(JP6-Pad22)") (class "Default")
      (node (ref "JP6") (pin "22") (pinfunction "22_22") (pintype "passive"))
    )
    (net (code "342") (name "unconnected-(JP6-Pad23)") (class "Default")
      (node (ref "JP6") (pin "23") (pinfunction "23_23") (pintype "passive"))
    )
    (net (code "343") (name "unconnected-(JP6-Pad24)") (class "Default")
      (node (ref "JP6") (pin "24") (pinfunction "24_24") (pintype "passive"))
    )
    (net (code "344") (name "unconnected-(JP6-Pad25)") (class "Default")
      (node (ref "JP6") (pin "25") (pinfunction "25_25") (pintype "passive"))
    )
    (net (code "345") (name "unconnected-(JP6-Pad26)") (class "Default")
      (node (ref "JP6") (pin "26") (pinfunction "26_26") (pintype "passive"))
    )
    (net (code "346") (name "unconnected-(JP6-Pad27)") (class "Default")
      (node (ref "JP6") (pin "27") (pinfunction "27_27") (pintype "passive"))
    )
    (net (code "347") (name "unconnected-(JP6-Pad28)") (class "Default")
      (node (ref "JP6") (pin "28") (pinfunction "28_28") (pintype "passive"))
    )
    (net (code "348") (name "unconnected-(JP6-Pad29)") (class "Default")
      (node (ref "JP6") (pin "29") (pinfunction "29_29") (pintype "passive"))
    )
    (net (code "349") (name "unconnected-(JP6-Pad30)") (class "Default")
      (node (ref "JP6") (pin "30") (pinfunction "30_30") (pintype "passive"))
    )
    (net (code "350") (name "unconnected-(JP6-Pad31)") (class "Default")
      (node (ref "JP6") (pin "31") (pinfunction "31_31") (pintype "passive"))
    )
    (net (code "351") (name "unconnected-(JP6-Pad32)") (class "Default")
      (node (ref "JP6") (pin "32") (pinfunction "32_32") (pintype "passive"))
    )
    (net (code "352") (name "unconnected-(JP6-Pad33)") (class "Default")
      (node (ref "JP6") (pin "33") (pinfunction "33_33") (pintype "passive"))
    )
    (net (code "353") (name "unconnected-(JP6-Pad34)") (class "Default")
      (node (ref "JP6") (pin "34") (pinfunction "34_34") (pintype "passive"))
    )
    (net (code "354") (name "unconnected-(JP6-Pad35)") (class "Default")
      (node (ref "JP6") (pin "35") (pinfunction "35_35") (pintype "passive"))
    )
    (net (code "355") (name "unconnected-(JP6-Pad36)") (class "Default")
      (node (ref "JP6") (pin "36") (pinfunction "36_36") (pintype "passive"))
    )
    (net (code "356") (name "unconnected-(JP6-Pad37)") (class "Default")
      (node (ref "JP6") (pin "37") (pinfunction "37_37") (pintype "passive"))
    )
    (net (code "357") (name "unconnected-(JP6-Pad38)") (class "Default")
      (node (ref "JP6") (pin "38") (pinfunction "38_38") (pintype "passive"))
    )
    (net (code "358") (name "unconnected-(JP6-Pad39)") (class "Default")
      (node (ref "JP6") (pin "39") (pinfunction "39_39") (pintype "passive"))
    )
    (net (code "359") (name "unconnected-(JP6-Pad40)") (class "Default")
      (node (ref "JP6") (pin "40") (pinfunction "40_40") (pintype "passive"))
    )
    (net (code "360") (name "unconnected-(JP6-Pad41)") (class "Default")
      (node (ref "JP6") (pin "41") (pinfunction "41_41") (pintype "passive"))
    )
    (net (code "361") (name "unconnected-(JP6-Pad42)") (class "Default")
      (node (ref "JP6") (pin "42") (pinfunction "42_42") (pintype "passive"))
    )
    (net (code "362") (name "unconnected-(JP6-Pad43)") (class "Default")
      (node (ref "JP6") (pin "43") (pinfunction "43_43") (pintype "passive"))
    )
    (net (code "363") (name "unconnected-(JP6-Pad44)") (class "Default")
      (node (ref "JP6") (pin "44") (pinfunction "44_44") (pintype "passive"))
    )
    (net (code "364") (name "unconnected-(JP6-Pad45)") (class "Default")
      (node (ref "JP6") (pin "45") (pinfunction "45_45") (pintype "passive"))
    )
    (net (code "365") (name "unconnected-(JP6-Pad46)") (class "Default")
      (node (ref "JP6") (pin "46") (pinfunction "46_46") (pintype "passive"))
    )
    (net (code "366") (name "unconnected-(JP6-Pad47)") (class "Default")
      (node (ref "JP6") (pin "47") (pinfunction "47_47") (pintype "passive"))
    )
    (net (code "367") (name "unconnected-(JP6-Pad48)") (class "Default")
      (node (ref "JP6") (pin "48") (pinfunction "48_48") (pintype "passive"))
    )
    (net (code "368") (name "unconnected-(X1K-S-Pad19)") (class "Default")
      (node (ref "X1") (pin "19") (pinfunction "S_19") (pintype "passive"))
    )
    (net (code "369") (name "unconnected-(X1M-S-Pad20)") (class "Default")
      (node (ref "X1") (pin "20") (pinfunction "S_20") (pintype "passive"))
    )
    (net (code "370") (name "unconnected-(X1N-S-Pad21)") (class "Default")
      (node (ref "X1") (pin "21") (pinfunction "S_21") (pintype "passive"))
    )
    (net (code "371") (name "unconnected-(X1O-S-Pad22)") (class "Default")
      (node (ref "X1") (pin "22") (pinfunction "S_22") (pintype "passive"))
    )
    (net (code "372") (name "unconnected-(X1P-S-Pad23)") (class "Default")
      (node (ref "X1") (pin "23") (pinfunction "S_23") (pintype "passive"))
    )
    (net (code "373") (name "unconnected-(X1Q-S-Pad24)") (class "Default")
      (node (ref "X1") (pin "24") (pinfunction "S_24") (pintype "passive"))
    )
    (net (code "374") (name "unconnected-(X1R-S-Pad25)") (class "Default")
      (node (ref "X1") (pin "25") (pinfunction "S_25") (pintype "passive"))
    )
    (net (code "375") (name "unconnected-(X1S-S-Pad26)") (class "Default")
      (node (ref "X1") (pin "26") (pinfunction "S_26") (pintype "passive"))
    )
  )
)
